# Stimulation_Testbed_Core_V1.net
KiCad netlist of a schematic drawn in EAGLE
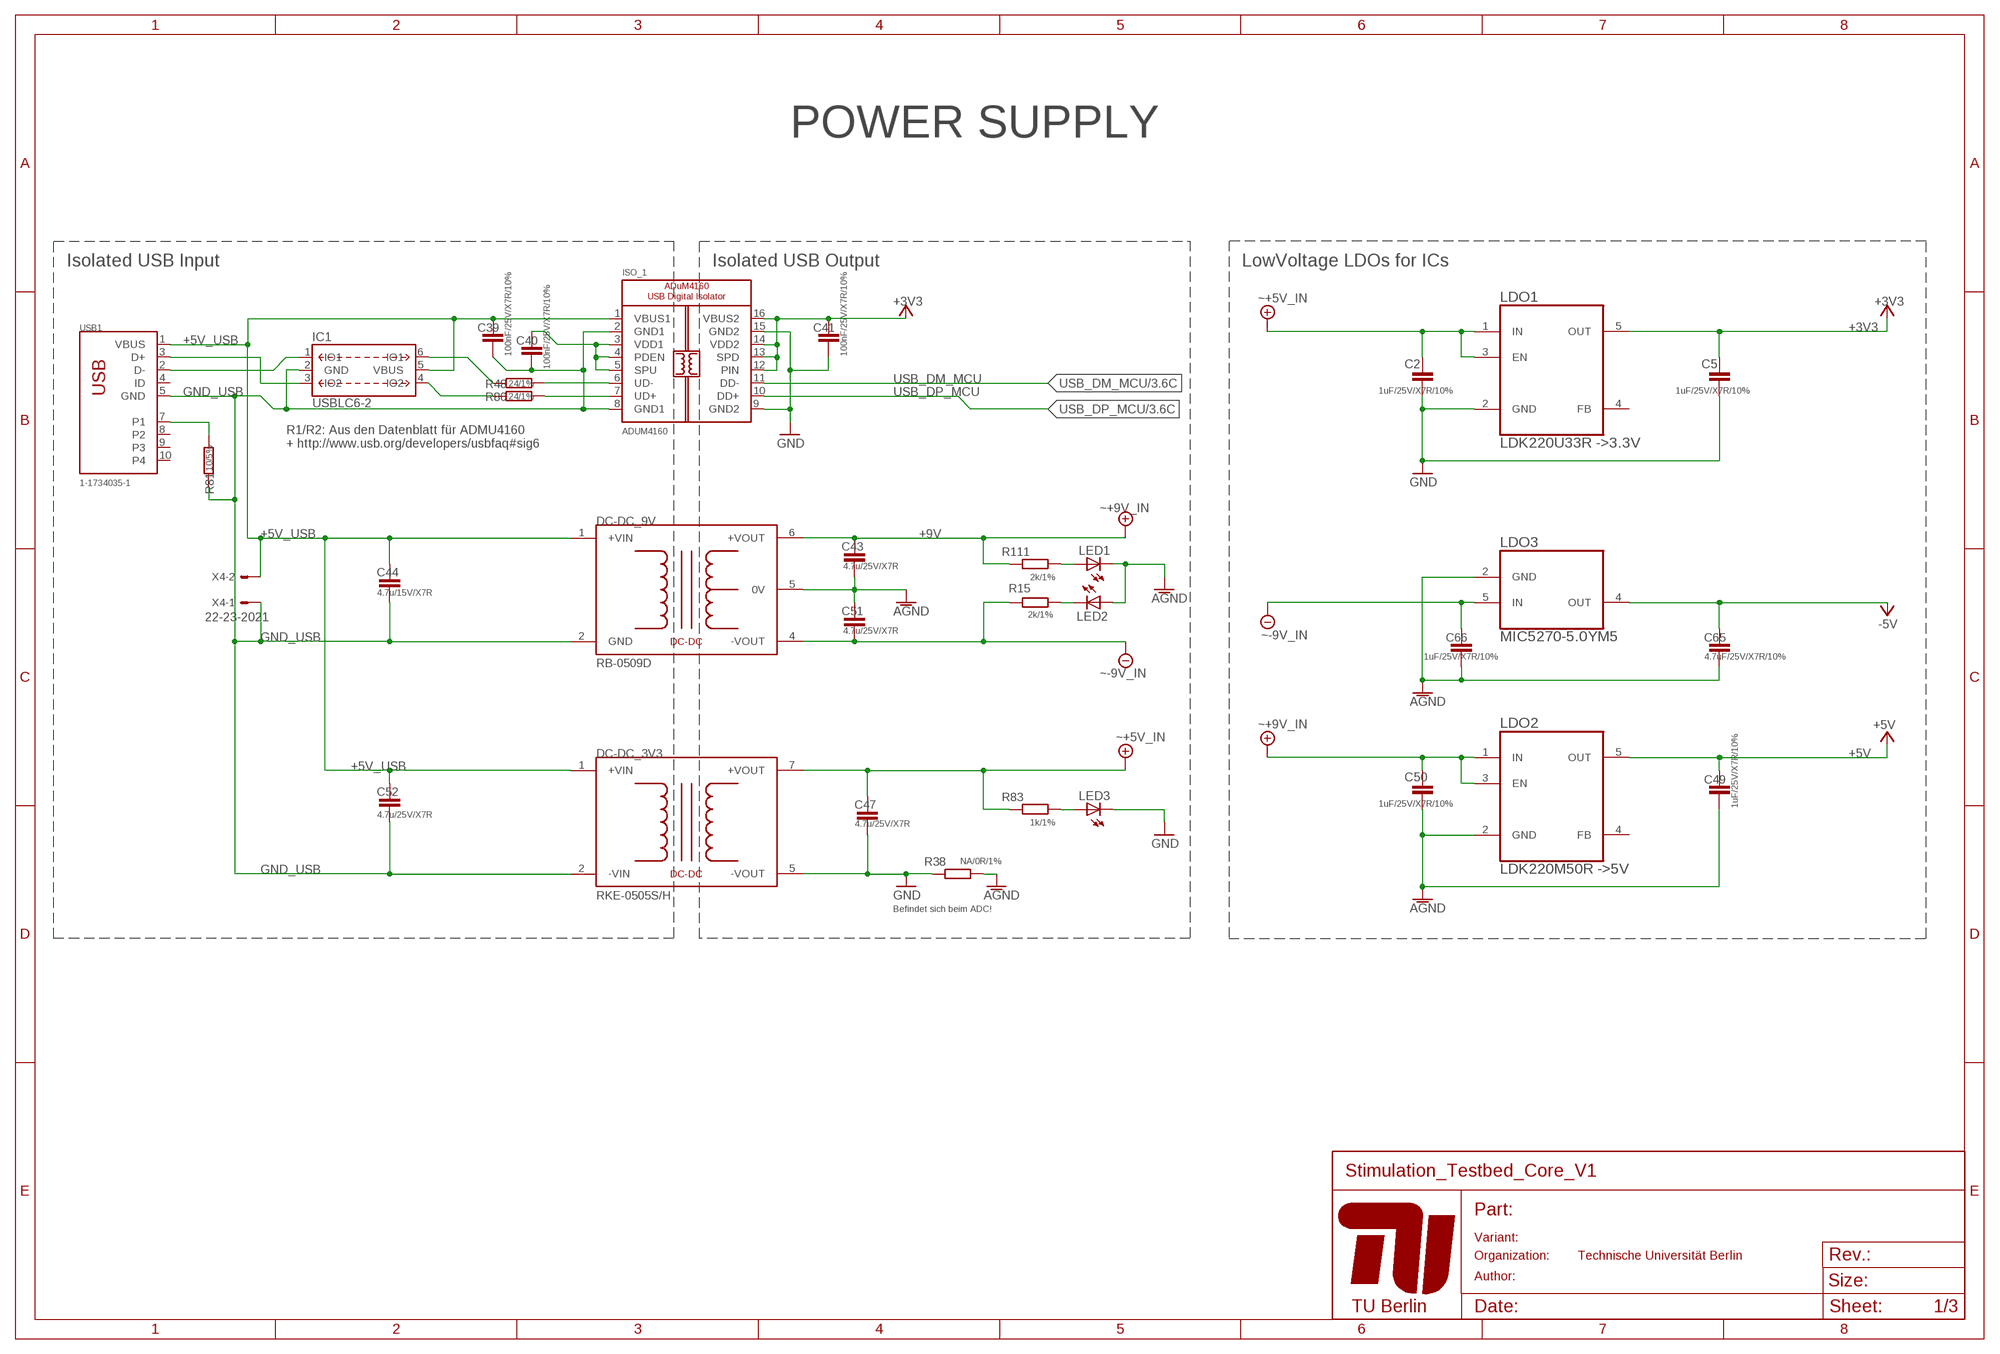
[diagram p0: schematic, sheet 1]
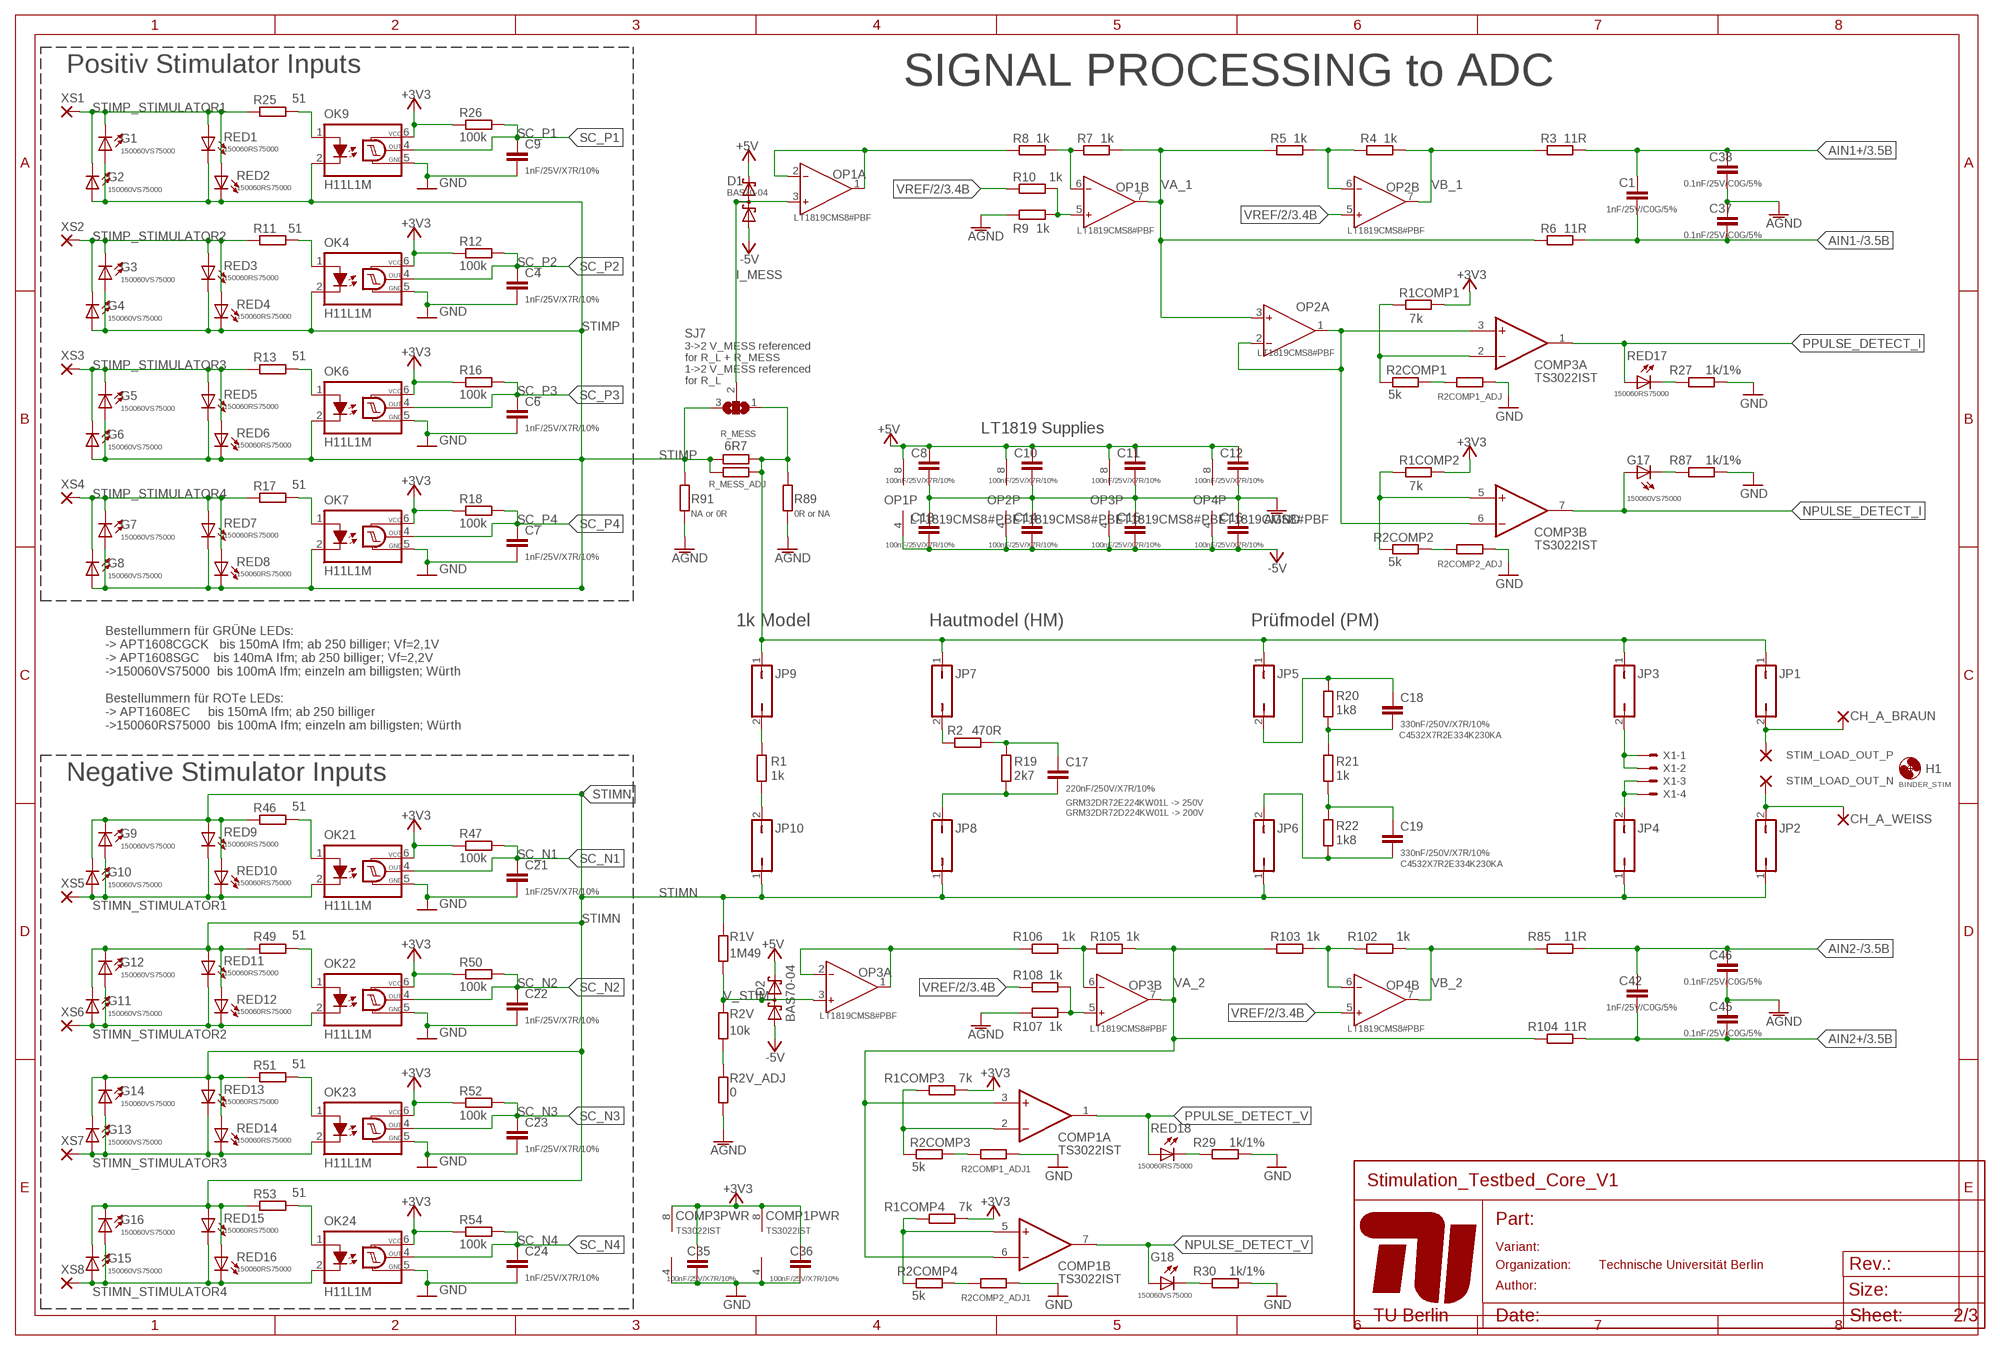
[diagram p1: schematic, sheet 2]
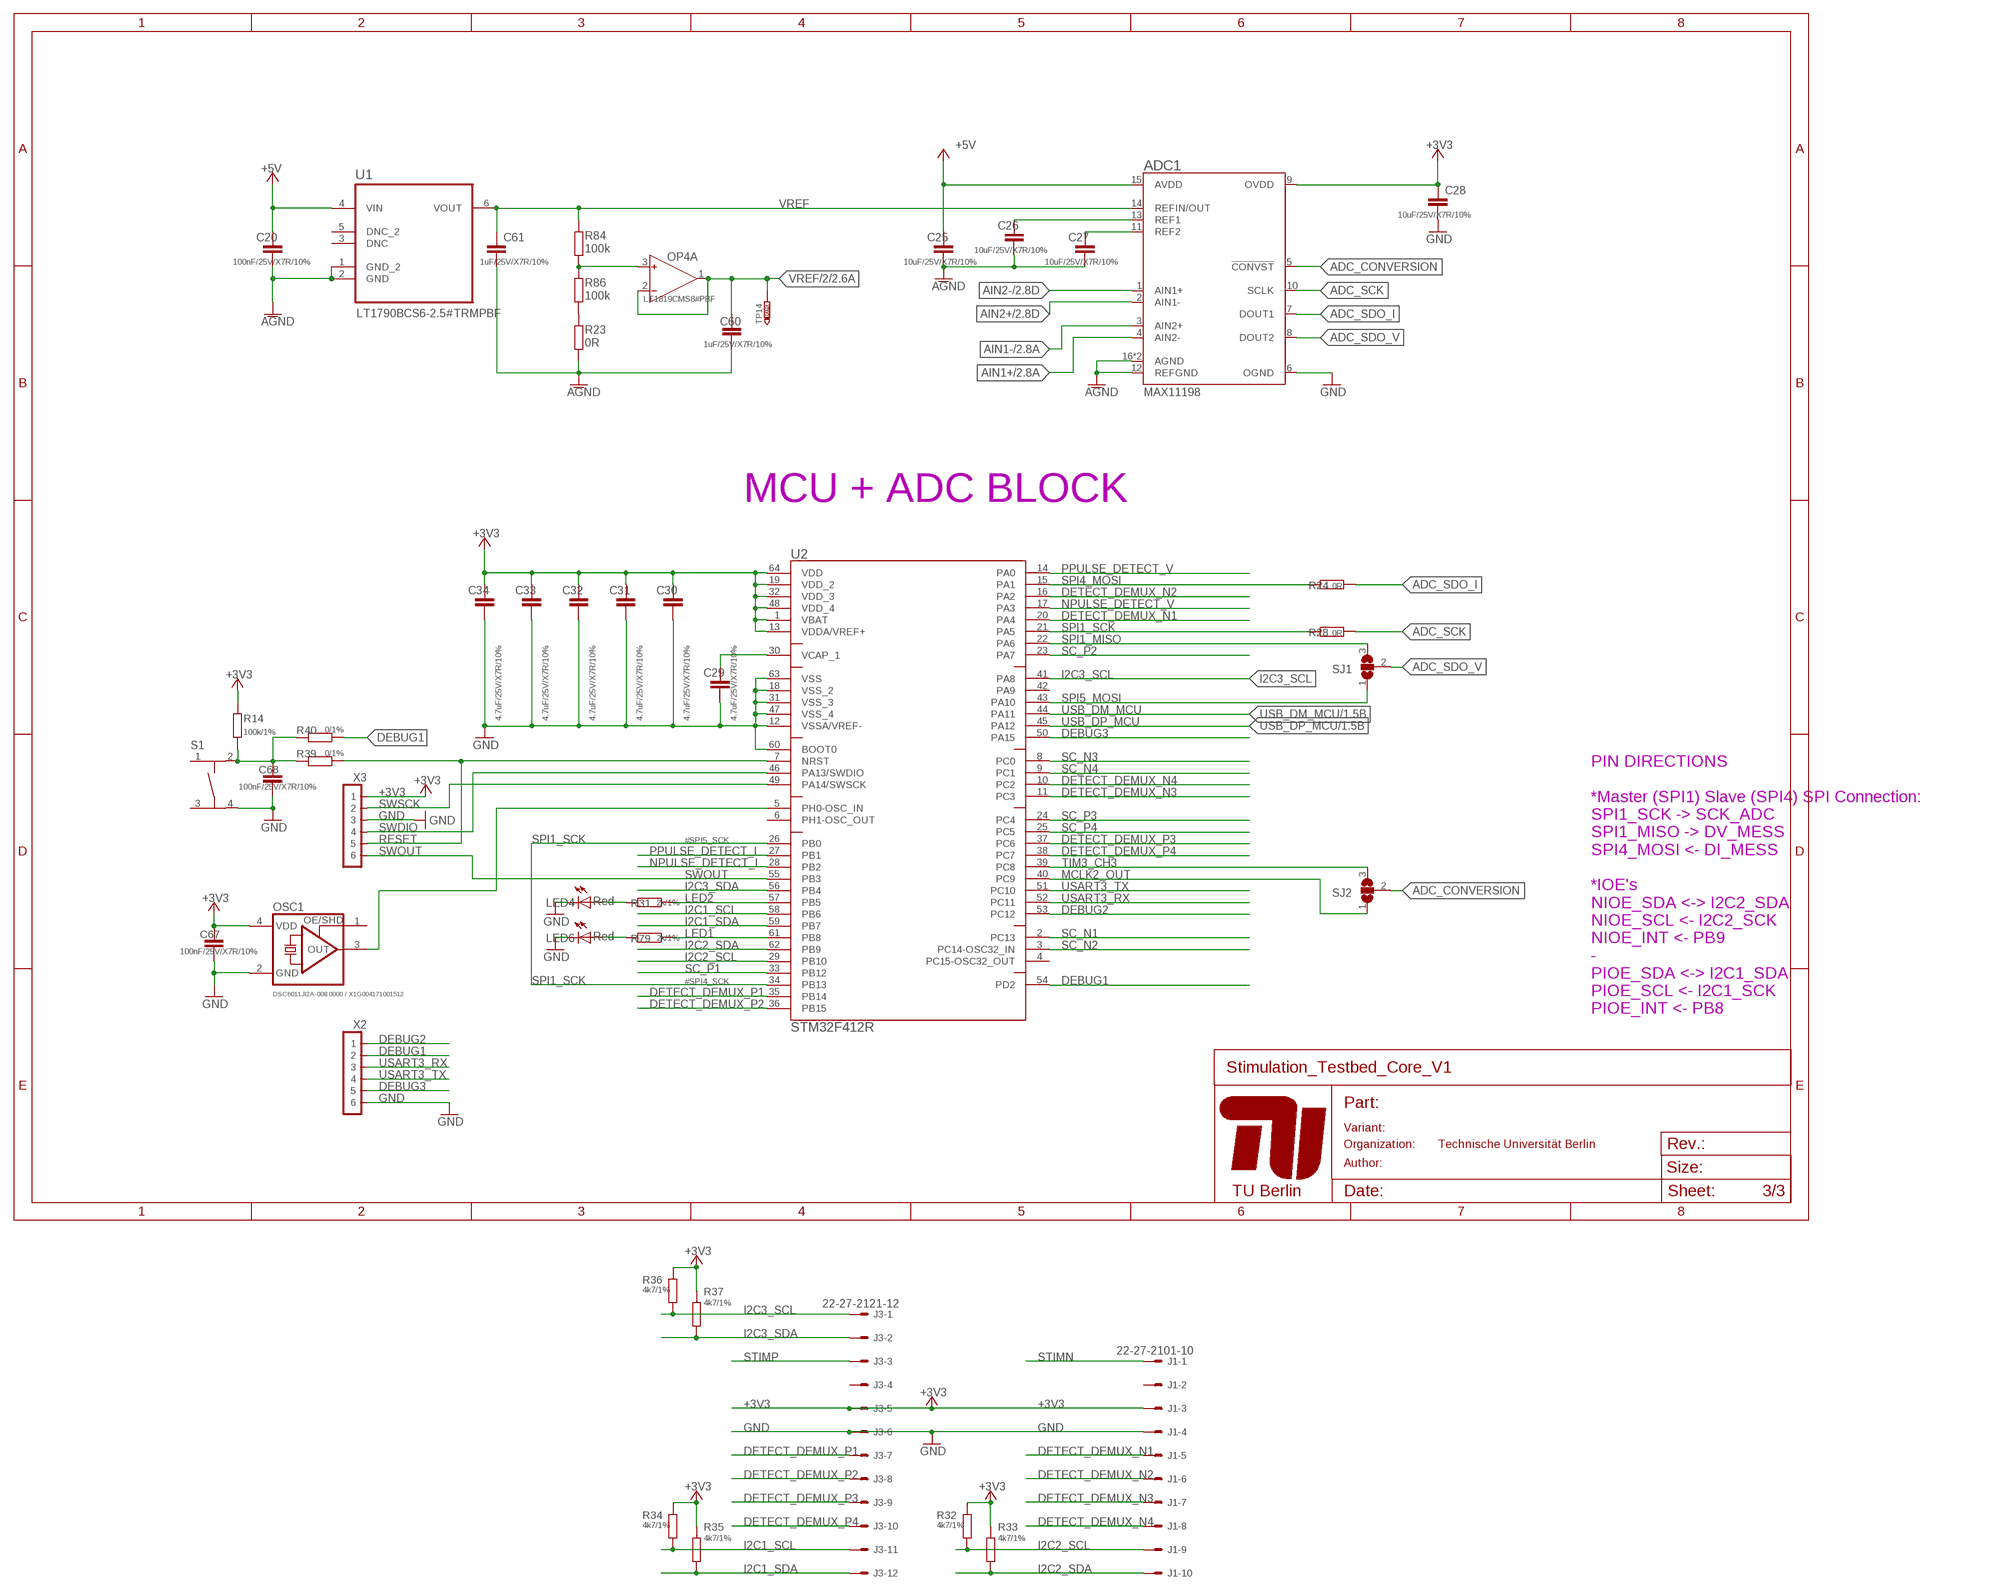
[diagram p2: schematic, sheet 3]

(export (version "E")
  (design (tool "Eeschema 10.0.6"))
  (components
    (comp (ref "ADC1")
      (value "MAX11198")
      (footprint "eagle-import:T1623CN+1")
      (libsource (lib "eagle-import") (part "MAX11198"))
    )
    (comp (ref "C20")
      (value "100nF/25V/X7R/10%")
      (footprint "eagle-import:C0603K")
      (libsource (lib "eagle-import") (part "C-EUC0603K"))
    )
    (comp (ref "C25")
      (value "10uF/25V/X7R/10%")
      (footprint "eagle-import:C0603K")
      (libsource (lib "eagle-import") (part "C-EUC0603K"))
    )
    (comp (ref "C26")
      (value "10uF/25V/X7R/10%")
      (footprint "eagle-import:C0603K")
      (libsource (lib "eagle-import") (part "C-EUC0603K"))
    )
    (comp (ref "C27")
      (value "10uF/25V/X7R/10%")
      (footprint "eagle-import:C0603K")
      (libsource (lib "eagle-import") (part "C-EUC0603K"))
    )
    (comp (ref "C28")
      (value "10uF/25V/X7R/10%")
      (footprint "eagle-import:C0603K")
      (libsource (lib "eagle-import") (part "C-EUC0603K"))
    )
    (comp (ref "C29")
      (value "4.7uF/25V/X7R/10%")
      (footprint "eagle-import:C0603K")
      (libsource (lib "eagle-import") (part "C-EUC0603K"))
    )
    (comp (ref "C30")
      (value "4.7uF/25V/X7R/10%")
      (footprint "eagle-import:C0603K")
      (libsource (lib "eagle-import") (part "C-EUC0603K"))
    )
    (comp (ref "C31")
      (value "4.7uF/25V/X7R/10%")
      (footprint "eagle-import:C0603K")
      (libsource (lib "eagle-import") (part "C-EUC0603K"))
    )
    (comp (ref "C32")
      (value "4.7uF/25V/X7R/10%")
      (footprint "eagle-import:C0603K")
      (libsource (lib "eagle-import") (part "C-EUC0603K"))
    )
    (comp (ref "C33")
      (value "4.7uF/25V/X7R/10%")
      (footprint "eagle-import:C0603K")
      (libsource (lib "eagle-import") (part "C-EUC0603K"))
    )
    (comp (ref "C34")
      (value "4.7uF/25V/X7R/10%")
      (footprint "eagle-import:C0603K")
      (libsource (lib "eagle-import") (part "C-EUC0603K"))
    )
    (comp (ref "C60")
      (value "1uF/25V/X7R/10%")
      (footprint "eagle-import:C0603K")
      (libsource (lib "eagle-import") (part "resistor_C-EUC0603K"))
    )
    (comp (ref "C61")
      (value "1uF/25V/X7R/10%")
      (footprint "eagle-import:C0603K")
      (libsource (lib "eagle-import") (part "resistor_C-EUC0603K"))
    )
    (comp (ref "C67")
      (value "100nF/25V/X7R/10%")
      (footprint "eagle-import:C0603K")
      (libsource (lib "eagle-import") (part "C-EUC0603K"))
    )
    (comp (ref "C68")
      (value "100nF/25V/X7R/10%")
      (footprint "eagle-import:C0603K")
      (libsource (lib "eagle-import") (part "C-EUC0603K"))
    )
    (comp (ref "J1")
      (value "22-27-2101-10")
      (footprint "eagle-import:6410-10")
      (libsource (lib "eagle-import") (part "22-?-1027-2101"))
    )
    (comp (ref "J3")
      (value "22-27-2121-12")
      (footprint "eagle-import:6410-12")
      (libsource (lib "eagle-import") (part "22-?-1227-2121"))
    )
    (comp (ref "LED4")
      (value "Red")
      (footprint "eagle-import:CHIPLED_0603")
      (libsource (lib "eagle-import") (part "LEDCHIPLED_0603"))
    )
    (comp (ref "LED6")
      (value "Red")
      (footprint "eagle-import:CHIPLED_0603")
      (libsource (lib "eagle-import") (part "LEDCHIPLED_0603"))
    )
    (comp (ref "OP4")
      (value "LT1819CMS8#PBF")
      (footprint "eagle-import:MSOP8")
      (libsource (lib "eagle-import") (part "LT1819"))
    )
    (comp (ref "OSC1")
      (value "DSC6011JI2A-008.0000 / X1G004171001512")
      (footprint "eagle-import:OSC_2.5X2")
      (libsource (lib "eagle-import") (part "OSC60XXX2.5X2"))
    )
    (comp (ref "R14")
      (value "100k/1%")
      (footprint "eagle-import:R0603")
      (libsource (lib "eagle-import") (part "R-EU_R0603"))
    )
    (comp (ref "R23")
      (value "0R")
      (footprint "eagle-import:R0603")
      (libsource (lib "eagle-import") (part "resistor_R-EU_R0603"))
    )
    (comp (ref "R24")
      (value "0R")
      (footprint "eagle-import:R0603")
      (libsource (lib "eagle-import") (part "R-EU_R0603"))
    )
    (comp (ref "R28")
      (value "0R")
      (footprint "eagle-import:R0603")
      (libsource (lib "eagle-import") (part "R-EU_R0603"))
    )
    (comp (ref "R31")
      (value "2k/1%")
      (footprint "eagle-import:R0603")
      (libsource (lib "eagle-import") (part "R-EU_R0603"))
    )
    (comp (ref "R32")
      (value "4k7/1%")
      (footprint "eagle-import:R0603")
      (libsource (lib "eagle-import") (part "R-EU_R0603"))
    )
    (comp (ref "R33")
      (value "4k7/1%")
      (footprint "eagle-import:R0603")
      (libsource (lib "eagle-import") (part "R-EU_R0603"))
    )
    (comp (ref "R34")
      (value "4k7/1%")
      (footprint "eagle-import:R0603")
      (libsource (lib "eagle-import") (part "R-EU_R0603"))
    )
    (comp (ref "R35")
      (value "4k7/1%")
      (footprint "eagle-import:R0603")
      (libsource (lib "eagle-import") (part "R-EU_R0603"))
    )
    (comp (ref "R36")
      (value "4k7/1%")
      (footprint "eagle-import:R0603")
      (libsource (lib "eagle-import") (part "R-EU_R0603"))
    )
    (comp (ref "R37")
      (value "4k7/1%")
      (footprint "eagle-import:R0603")
      (libsource (lib "eagle-import") (part "R-EU_R0603"))
    )
    (comp (ref "R39")
      (value "0/1%")
      (footprint "eagle-import:R0603")
      (libsource (lib "eagle-import") (part "R-EU_R0603"))
    )
    (comp (ref "R40")
      (value "0/1%")
      (footprint "eagle-import:R0603")
      (libsource (lib "eagle-import") (part "R-EU_R0603"))
    )
    (comp (ref "R79")
      (value "2k/1%")
      (footprint "eagle-import:R0603")
      (libsource (lib "eagle-import") (part "R-EU_R0603"))
    )
    (comp (ref "R84")
      (value "100k")
      (footprint "eagle-import:R0603")
      (libsource (lib "eagle-import") (part "resistor_R-EU_R0603"))
    )
    (comp (ref "R86")
      (value "100k")
      (footprint "eagle-import:R0603")
      (libsource (lib "eagle-import") (part "resistor_R-EU_R0603"))
    )
    (comp (ref "S1")
      (value "TASTERSMD")
      (footprint "eagle-import:TAST_SMD")
      (libsource (lib "eagle-import") (part "TASTERSMD"))
    )
    (comp (ref "SJ1")
      (value "SJ2W")
      (footprint "eagle-import:SJ_2")
      (libsource (lib "eagle-import") (part "SJ2W"))
    )
    (comp (ref "SJ2")
      (value "SJ2W")
      (footprint "eagle-import:SJ_2")
      (libsource (lib "eagle-import") (part "SJ2W"))
    )
    (comp (ref "TP14")
      (value "TESTPOINT_TH")
      (footprint "eagle-import:TP1-09")
      (libsource (lib "eagle-import") (part "TESTPOINT_TH"))
    )
    (comp (ref "U1")
      (value "LT1790BCS6-2.5#TRMPBF")
      (footprint "eagle-import:SOT95P280X100-6N")
      (fields (field (name "MF") "Linear Technology") (field (name "MP") "LT1790ACS6-2.5#PBF"))
      (libsource (lib "eagle-import") (part "LT1790ACS6-2.5PBF"))
    )
    (comp (ref "U2")
      (value "STM32F412R")
      (footprint "eagle-import:LQFP64-10X10MM")
      (fields (field (name "MANUFACTURER_PART_NUMBER") "stm32f4xxr2"))
      (libsource (lib "eagle-import") (part "STM32F4XXR"))
    )
    (comp (ref "X2")
      (value "PINHD-1X66X1.27")
      (footprint "eagle-import:1.27_1X06_S")
      (libsource (lib "eagle-import") (part "PINHD-1X66X1.27"))
    )
    (comp (ref "X3")
      (value "PINHD-1X66X1.27")
      (footprint "eagle-import:1.27_1X06_S")
      (libsource (lib "eagle-import") (part "PINHD-1X66X1.27"))
    )
    (comp (ref "C1")
      (value "1nF/25V/C0G/5%")
      (footprint "eagle-import:C0603K")
      (libsource (lib "eagle-import") (part "resistor_C-EUC0603K"))
    )
    (comp (ref "C4")
      (value "1nF/25V/X7R/10%")
      (footprint "eagle-import:C0603")
      (libsource (lib "eagle-import") (part "C-EUC0603"))
    )
    (comp (ref "C6")
      (value "1nF/25V/X7R/10%")
      (footprint "eagle-import:C0603")
      (libsource (lib "eagle-import") (part "C-EUC0603"))
    )
    (comp (ref "C7")
      (value "1nF/25V/X7R/10%")
      (footprint "eagle-import:C0603")
      (libsource (lib "eagle-import") (part "C-EUC0603"))
    )
    (comp (ref "C8")
      (value "100nF/25V/X7R/10%")
      (footprint "eagle-import:C0603K")
      (libsource (lib "eagle-import") (part "C-EUC0603K"))
    )
    (comp (ref "C9")
      (value "1nF/25V/X7R/10%")
      (footprint "eagle-import:C0603")
      (libsource (lib "eagle-import") (part "C-EUC0603"))
    )
    (comp (ref "C10")
      (value "100nF/25V/X7R/10%")
      (footprint "eagle-import:C0603K")
      (libsource (lib "eagle-import") (part "C-EUC0603K"))
    )
    (comp (ref "C11")
      (value "100nF/25V/X7R/10%")
      (footprint "eagle-import:C0603K")
      (libsource (lib "eagle-import") (part "C-EUC0603K"))
    )
    (comp (ref "C12")
      (value "100nF/25V/X7R/10%")
      (footprint "eagle-import:C0603K")
      (libsource (lib "eagle-import") (part "C-EUC0603K"))
    )
    (comp (ref "C13")
      (value "100nF/25V/X7R/10%")
      (footprint "eagle-import:C0603K")
      (libsource (lib "eagle-import") (part "C-EUC0603K"))
    )
    (comp (ref "C14")
      (value "100nF/25V/X7R/10%")
      (footprint "eagle-import:C0603K")
      (libsource (lib "eagle-import") (part "C-EUC0603K"))
    )
    (comp (ref "C15")
      (value "100nF/25V/X7R/10%")
      (footprint "eagle-import:C0603K")
      (libsource (lib "eagle-import") (part "C-EUC0603K"))
    )
    (comp (ref "C16")
      (value "100nF/25V/X7R/10%")
      (footprint "eagle-import:C0603K")
      (libsource (lib "eagle-import") (part "C-EUC0603K"))
    )
    (comp (ref "C17")
      (value "220nF/250V/X7R/10%")
      (footprint "eagle-import:C1210")
      (libsource (lib "eagle-import") (part "resistor_C-EUC1210"))
    )
    (comp (ref "C18")
      (value "330nF/250V/X7R/10%")
      (footprint "eagle-import:C1812")
      (libsource (lib "eagle-import") (part "resistor_C-EUC1812"))
    )
    (comp (ref "C19")
      (value "330nF/250V/X7R/10%")
      (footprint "eagle-import:C1812")
      (libsource (lib "eagle-import") (part "resistor_C-EUC1812"))
    )
    (comp (ref "C21")
      (value "1nF/25V/X7R/10%")
      (footprint "eagle-import:C0603")
      (libsource (lib "eagle-import") (part "C-EUC0603"))
    )
    (comp (ref "C22")
      (value "1nF/25V/X7R/10%")
      (footprint "eagle-import:C0603")
      (libsource (lib "eagle-import") (part "C-EUC0603"))
    )
    (comp (ref "C23")
      (value "1nF/25V/X7R/10%")
      (footprint "eagle-import:C0603")
      (libsource (lib "eagle-import") (part "C-EUC0603"))
    )
    (comp (ref "C24")
      (value "1nF/25V/X7R/10%")
      (footprint "eagle-import:C0603")
      (libsource (lib "eagle-import") (part "C-EUC0603"))
    )
    (comp (ref "C35")
      (value "100nF/25V/X7R/10%")
      (footprint "eagle-import:C0603K")
      (libsource (lib "eagle-import") (part "C-EUC0603K"))
    )
    (comp (ref "C36")
      (value "100nF/25V/X7R/10%")
      (footprint "eagle-import:C0603K")
      (libsource (lib "eagle-import") (part "C-EUC0603K"))
    )
    (comp (ref "C37")
      (value "0.1nF/25V/C0G/5%")
      (footprint "eagle-import:C0603K")
      (libsource (lib "eagle-import") (part "resistor_C-EUC0603K"))
    )
    (comp (ref "C38")
      (value "0.1nF/25V/C0G/5%")
      (footprint "eagle-import:C0603K")
      (libsource (lib "eagle-import") (part "resistor_C-EUC0603K"))
    )
    (comp (ref "C42")
      (value "1nF/25V/C0G/5%")
      (footprint "eagle-import:C0603K")
      (libsource (lib "eagle-import") (part "resistor_C-EUC0603K"))
    )
    (comp (ref "C45")
      (value "0.1nF/25V/C0G/5%")
      (footprint "eagle-import:C0603K")
      (libsource (lib "eagle-import") (part "resistor_C-EUC0603K"))
    )
    (comp (ref "C46")
      (value "0.1nF/25V/C0G/5%")
      (footprint "eagle-import:C0603K")
      (libsource (lib "eagle-import") (part "resistor_C-EUC0603K"))
    )
    (comp (ref "CH_A_BRAUN")
      (value "1,6/0,8")
      (footprint "eagle-import:1,6_0,8")
      (libsource (lib "eagle-import") (part "1,6/0,8"))
    )
    (comp (ref "CH_A_WEISS")
      (value "1,6/0,8")
      (footprint "eagle-import:1,6_0,8")
      (libsource (lib "eagle-import") (part "1,6/0,8"))
    )
    (comp (ref "COMP1")
      (value "TS3022IST")
      (footprint "eagle-import:MSOP8")
      (libsource (lib "eagle-import") (part "TS3022IST"))
    )
    (comp (ref "COMP3")
      (value "TS3022IST")
      (footprint "eagle-import:MSOP8")
      (libsource (lib "eagle-import") (part "TS3022IST"))
    )
    (comp (ref "D1")
      (value "BAS70-04")
      (footprint "eagle-import:SOT23")
      (libsource (lib "eagle-import") (part "BAS70-04"))
    )
    (comp (ref "D2")
      (value "BAS70-04")
      (footprint "eagle-import:SOT23")
      (libsource (lib "eagle-import") (part "BAS70-04"))
    )
    (comp (ref "G1")
      (value "150060VS75000")
      (footprint "eagle-import:CHIPLED_0603")
      (libsource (lib "eagle-import") (part "LEDCHIPLED_0603"))
    )
    (comp (ref "G2")
      (value "150060VS75000")
      (footprint "eagle-import:CHIPLED_0603")
      (libsource (lib "eagle-import") (part "LEDCHIPLED_0603"))
    )
    (comp (ref "G3")
      (value "150060VS75000")
      (footprint "eagle-import:CHIPLED_0603")
      (libsource (lib "eagle-import") (part "LEDCHIPLED_0603"))
    )
    (comp (ref "G4")
      (value "150060VS75000")
      (footprint "eagle-import:CHIPLED_0603")
      (libsource (lib "eagle-import") (part "LEDCHIPLED_0603"))
    )
    (comp (ref "G5")
      (value "150060VS75000")
      (footprint "eagle-import:CHIPLED_0603")
      (libsource (lib "eagle-import") (part "LEDCHIPLED_0603"))
    )
    (comp (ref "G6")
      (value "150060VS75000")
      (footprint "eagle-import:CHIPLED_0603")
      (libsource (lib "eagle-import") (part "LEDCHIPLED_0603"))
    )
    (comp (ref "G7")
      (value "150060VS75000")
      (footprint "eagle-import:CHIPLED_0603")
      (libsource (lib "eagle-import") (part "LEDCHIPLED_0603"))
    )
    (comp (ref "G8")
      (value "150060VS75000")
      (footprint "eagle-import:CHIPLED_0603")
      (libsource (lib "eagle-import") (part "LEDCHIPLED_0603"))
    )
    (comp (ref "G9")
      (value "150060VS75000")
      (footprint "eagle-import:CHIPLED_0603")
      (libsource (lib "eagle-import") (part "LEDCHIPLED_0603"))
    )
    (comp (ref "G10")
      (value "150060VS75000")
      (footprint "eagle-import:CHIPLED_0603")
      (libsource (lib "eagle-import") (part "LEDCHIPLED_0603"))
    )
    (comp (ref "G11")
      (value "150060VS75000")
      (footprint "eagle-import:CHIPLED_0603")
      (libsource (lib "eagle-import") (part "LEDCHIPLED_0603"))
    )
    (comp (ref "G12")
      (value "150060VS75000")
      (footprint "eagle-import:CHIPLED_0603")
      (libsource (lib "eagle-import") (part "LEDCHIPLED_0603"))
    )
    (comp (ref "G13")
      (value "150060VS75000")
      (footprint "eagle-import:CHIPLED_0603")
      (libsource (lib "eagle-import") (part "LEDCHIPLED_0603"))
    )
    (comp (ref "G14")
      (value "150060VS75000")
      (footprint "eagle-import:CHIPLED_0603")
      (libsource (lib "eagle-import") (part "LEDCHIPLED_0603"))
    )
    (comp (ref "G15")
      (value "150060VS75000")
      (footprint "eagle-import:CHIPLED_0603")
      (libsource (lib "eagle-import") (part "LEDCHIPLED_0603"))
    )
    (comp (ref "G16")
      (value "150060VS75000")
      (footprint "eagle-import:CHIPLED_0603")
      (libsource (lib "eagle-import") (part "LEDCHIPLED_0603"))
    )
    (comp (ref "G17")
      (value "150060VS75000")
      (footprint "eagle-import:CHIPLED_0603")
      (libsource (lib "eagle-import") (part "LEDCHIPLED_0603"))
    )
    (comp (ref "G18")
      (value "150060VS75000")
      (footprint "eagle-import:CHIPLED_0603")
      (libsource (lib "eagle-import") (part "LEDCHIPLED_0603"))
    )
    (comp (ref "H1")
      (value "BINDER_STIM")
      (footprint "eagle-import:5,5-PAD")
      (libsource (lib "eagle-import") (part "BINDER_STIM"))
    )
    (comp (ref "JP1")
      (value "JP1Q")
      (footprint "eagle-import:JP1")
      (libsource (lib "eagle-import") (part "JP1Q"))
    )
    (comp (ref "JP2")
      (value "JP1Q")
      (footprint "eagle-import:JP1")
      (libsource (lib "eagle-import") (part "JP1Q"))
    )
    (comp (ref "JP3")
      (value "JP1Q")
      (footprint "eagle-import:JP1")
      (libsource (lib "eagle-import") (part "JP1Q"))
    )
    (comp (ref "JP4")
      (value "JP1Q")
      (footprint "eagle-import:JP1")
      (libsource (lib "eagle-import") (part "JP1Q"))
    )
    (comp (ref "JP5")
      (value "JP1Q")
      (footprint "eagle-import:JP1")
      (libsource (lib "eagle-import") (part "JP1Q"))
    )
    (comp (ref "JP6")
      (value "JP1Q")
      (footprint "eagle-import:JP1")
      (libsource (lib "eagle-import") (part "JP1Q"))
    )
    (comp (ref "JP7")
      (value "JP1Q")
      (footprint "eagle-import:JP1")
      (libsource (lib "eagle-import") (part "JP1Q"))
    )
    (comp (ref "JP8")
      (value "JP1Q")
      (footprint "eagle-import:JP1")
      (libsource (lib "eagle-import") (part "JP1Q"))
    )
    (comp (ref "JP9")
      (value "JP1Q")
      (footprint "eagle-import:JP1")
      (libsource (lib "eagle-import") (part "JP1Q"))
    )
    (comp (ref "JP10")
      (value "JP1Q")
      (footprint "eagle-import:JP1")
      (libsource (lib "eagle-import") (part "JP1Q"))
    )
    (comp (ref "OK4")
      (value "H11L1M")
      (footprint "eagle-import:DIL06")
      (fields (field (name "MF") "FAIRCHILD SEMICONDUCTOR") (field (name "MPN") "H11L1-M"))
      (libsource (lib "eagle-import") (part "H11LM1"))
    )
    (comp (ref "OK6")
      (value "H11L1M")
      (footprint "eagle-import:DIL06")
      (fields (field (name "MF") "FAIRCHILD SEMICONDUCTOR") (field (name "MPN") "H11L1-M"))
      (libsource (lib "eagle-import") (part "H11LM1"))
    )
    (comp (ref "OK7")
      (value "H11L1M")
      (footprint "eagle-import:DIL06")
      (fields (field (name "MF") "FAIRCHILD SEMICONDUCTOR") (field (name "MPN") "H11L1-M"))
      (libsource (lib "eagle-import") (part "H11LM1"))
    )
    (comp (ref "OK9")
      (value "H11L1M")
      (footprint "eagle-import:DIL06")
      (fields (field (name "MF") "FAIRCHILD SEMICONDUCTOR") (field (name "MPN") "H11L1-M"))
      (libsource (lib "eagle-import") (part "H11LM1"))
    )
    (comp (ref "OK21")
      (value "H11L1M")
      (footprint "eagle-import:DIL06")
      (fields (field (name "MF") "FAIRCHILD SEMICONDUCTOR") (field (name "MPN") "H11L1-M"))
      (libsource (lib "eagle-import") (part "H11LM1"))
    )
    (comp (ref "OK22")
      (value "H11L1M")
      (footprint "eagle-import:DIL06")
      (fields (field (name "MF") "FAIRCHILD SEMICONDUCTOR") (field (name "MPN") "H11L1-M"))
      (libsource (lib "eagle-import") (part "H11LM1"))
    )
    (comp (ref "OK23")
      (value "H11L1M")
      (footprint "eagle-import:DIL06")
      (fields (field (name "MF") "FAIRCHILD SEMICONDUCTOR") (field (name "MPN") "H11L1-M"))
      (libsource (lib "eagle-import") (part "H11LM1"))
    )
    (comp (ref "OK24")
      (value "H11L1M")
      (footprint "eagle-import:DIL06")
      (fields (field (name "MF") "FAIRCHILD SEMICONDUCTOR") (field (name "MPN") "H11L1-M"))
      (libsource (lib "eagle-import") (part "H11LM1"))
    )
    (comp (ref "OP1")
      (value "LT1819CMS8#PBF")
      (footprint "eagle-import:MSOP8")
      (libsource (lib "eagle-import") (part "LT1819"))
    )
    (comp (ref "OP2")
      (value "LT1819CMS8#PBF")
      (footprint "eagle-import:MSOP8")
      (libsource (lib "eagle-import") (part "LT1819"))
    )
    (comp (ref "OP3")
      (value "LT1819CMS8#PBF")
      (footprint "eagle-import:MSOP8")
      (libsource (lib "eagle-import") (part "LT1819"))
    )
    (comp (ref "R1")
      (value "1k")
      (footprint "eagle-import:R1206")
      (libsource (lib "eagle-import") (part "resistor_R-EU_R1206"))
    )
    (comp (ref "R1COMP1")
      (value "7k")
      (footprint "eagle-import:R0603")
      (libsource (lib "eagle-import") (part "resistor_R-EU_R0603"))
    )
    (comp (ref "R1COMP2")
      (value "7k")
      (footprint "eagle-import:R0603")
      (libsource (lib "eagle-import") (part "resistor_R-EU_R0603"))
    )
    (comp (ref "R1COMP3")
      (value "7k")
      (footprint "eagle-import:R0603")
      (libsource (lib "eagle-import") (part "resistor_R-EU_R0603"))
    )
    (comp (ref "R1COMP4")
      (value "7k")
      (footprint "eagle-import:R0603")
      (libsource (lib "eagle-import") (part "resistor_R-EU_R0603"))
    )
    (comp (ref "R1V")
      (value "1M49")
      (footprint "eagle-import:R1206")
      (libsource (lib "eagle-import") (part "resistor_R-EU_R1206"))
    )
    (comp (ref "R2")
      (value "470R")
      (footprint "eagle-import:R1206")
      (libsource (lib "eagle-import") (part "resistor_R-EU_R1206"))
    )
    (comp (ref "R2COMP1")
      (value "5k")
      (footprint "eagle-import:R0603")
      (libsource (lib "eagle-import") (part "resistor_R-EU_R0603"))
    )
    (comp (ref "R2COMP1_ADJ")
      (value "R-EU_R0603")
      (footprint "eagle-import:R0603")
      (libsource (lib "eagle-import") (part "resistor_R-EU_R0603"))
    )
    (comp (ref "R2COMP1_ADJ1")
      (value "R-EU_R0603")
      (footprint "eagle-import:R0603")
      (libsource (lib "eagle-import") (part "resistor_R-EU_R0603"))
    )
    (comp (ref "R2COMP2")
      (value "5k")
      (footprint "eagle-import:R0603")
      (libsource (lib "eagle-import") (part "resistor_R-EU_R0603"))
    )
    (comp (ref "R2COMP2_ADJ")
      (value "1k")
      (footprint "eagle-import:R0603")
      (libsource (lib "eagle-import") (part "resistor_R-EU_R0603"))
    )
    (comp (ref "R2COMP2_ADJ1")
      (value "1k")
      (footprint "eagle-import:R0603")
      (libsource (lib "eagle-import") (part "resistor_R-EU_R0603"))
    )
    (comp (ref "R2COMP3")
      (value "5k")
      (footprint "eagle-import:R0603")
      (libsource (lib "eagle-import") (part "resistor_R-EU_R0603"))
    )
    (comp (ref "R2COMP4")
      (value "5k")
      (footprint "eagle-import:R0603")
      (libsource (lib "eagle-import") (part "resistor_R-EU_R0603"))
    )
    (comp (ref "R2V")
      (value "10k")
      (footprint "eagle-import:R1206")
      (libsource (lib "eagle-import") (part "resistor_R-EU_R1206"))
    )
    (comp (ref "R2V_ADJ")
      (value "0")
      (footprint "eagle-import:R1206")
      (libsource (lib "eagle-import") (part "resistor_R-EU_R1206"))
    )
    (comp (ref "R3")
      (value "11R")
      (footprint "eagle-import:R0603")
      (libsource (lib "eagle-import") (part "resistor_R-EU_R0603"))
    )
    (comp (ref "R4")
      (value "1k")
      (footprint "eagle-import:R0603")
      (libsource (lib "eagle-import") (part "resistor_R-EU_R0603"))
    )
    (comp (ref "R5")
      (value "1k")
      (footprint "eagle-import:R0603")
      (libsource (lib "eagle-import") (part "resistor_R-EU_R0603"))
    )
    (comp (ref "R6")
      (value "11R")
      (footprint "eagle-import:R0603")
      (libsource (lib "eagle-import") (part "resistor_R-EU_R0603"))
    )
    (comp (ref "R7")
      (value "1k")
      (footprint "eagle-import:R0603")
      (libsource (lib "eagle-import") (part "resistor_R-EU_R0603"))
    )
    (comp (ref "R8")
      (value "1k")
      (footprint "eagle-import:R0603")
      (libsource (lib "eagle-import") (part "resistor_R-EU_R0603"))
    )
    (comp (ref "R9")
      (value "1k")
      (footprint "eagle-import:R0603")
      (libsource (lib "eagle-import") (part "resistor_R-EU_R0603"))
    )
    (comp (ref "R10")
      (value "1k")
      (footprint "eagle-import:R0603")
      (libsource (lib "eagle-import") (part "resistor_R-EU_R0603"))
    )
    (comp (ref "R11")
      (value "51")
      (footprint "eagle-import:R0603")
      (libsource (lib "eagle-import") (part "resistor_R-EU_R0603"))
    )
    (comp (ref "R12")
      (value "100k")
      (footprint "eagle-import:R0603")
      (libsource (lib "eagle-import") (part "resistor_R-EU_R0603"))
    )
    (comp (ref "R13")
      (value "51")
      (footprint "eagle-import:R0603")
      (libsource (lib "eagle-import") (part "resistor_R-EU_R0603"))
    )
    (comp (ref "R16")
      (value "100k")
      (footprint "eagle-import:R0603")
      (libsource (lib "eagle-import") (part "resistor_R-EU_R0603"))
    )
    (comp (ref "R17")
      (value "51")
      (footprint "eagle-import:R0603")
      (libsource (lib "eagle-import") (part "resistor_R-EU_R0603"))
    )
    (comp (ref "R18")
      (value "100k")
      (footprint "eagle-import:R0603")
      (libsource (lib "eagle-import") (part "resistor_R-EU_R0603"))
    )
    (comp (ref "R19")
      (value "2k7")
      (footprint "eagle-import:R1206")
      (libsource (lib "eagle-import") (part "resistor_R-EU_R1206"))
    )
    (comp (ref "R20")
      (value "1k8")
      (footprint "eagle-import:R1206")
      (libsource (lib "eagle-import") (part "resistor_R-EU_R1206"))
    )
    (comp (ref "R21")
      (value "1k")
      (footprint "eagle-import:R1206")
      (libsource (lib "eagle-import") (part "resistor_R-EU_R1206"))
    )
    (comp (ref "R22")
      (value "1k8")
      (footprint "eagle-import:R1206")
      (libsource (lib "eagle-import") (part "resistor_R-EU_R1206"))
    )
    (comp (ref "R25")
      (value "51")
      (footprint "eagle-import:R0603")
      (libsource (lib "eagle-import") (part "resistor_R-EU_R0603"))
    )
    (comp (ref "R26")
      (value "100k")
      (footprint "eagle-import:R0603")
      (libsource (lib "eagle-import") (part "resistor_R-EU_R0603"))
    )
    (comp (ref "R27")
      (value "1k/1%")
      (footprint "eagle-import:R0603")
      (libsource (lib "eagle-import") (part "resistor_R-EU_R0603"))
    )
    (comp (ref "R29")
      (value "1k/1%")
      (footprint "eagle-import:R0603")
      (libsource (lib "eagle-import") (part "resistor_R-EU_R0603"))
    )
    (comp (ref "R30")
      (value "1k/1%")
      (footprint "eagle-import:R0603")
      (libsource (lib "eagle-import") (part "resistor_R-EU_R0603"))
    )
    (comp (ref "R46")
      (value "51")
      (footprint "eagle-import:R0603")
      (libsource (lib "eagle-import") (part "resistor_R-EU_R0603"))
    )
    (comp (ref "R47")
      (value "100k")
      (footprint "eagle-import:R0603")
      (libsource (lib "eagle-import") (part "resistor_R-EU_R0603"))
    )
    (comp (ref "R49")
      (value "51")
      (footprint "eagle-import:R0603")
      (libsource (lib "eagle-import") (part "resistor_R-EU_R0603"))
    )
    (comp (ref "R50")
      (value "100k")
      (footprint "eagle-import:R0603")
      (libsource (lib "eagle-import") (part "resistor_R-EU_R0603"))
    )
    (comp (ref "R51")
      (value "51")
      (footprint "eagle-import:R0603")
      (libsource (lib "eagle-import") (part "resistor_R-EU_R0603"))
    )
    (comp (ref "R52")
      (value "100k")
      (footprint "eagle-import:R0603")
      (libsource (lib "eagle-import") (part "resistor_R-EU_R0603"))
    )
    (comp (ref "R53")
      (value "51")
      (footprint "eagle-import:R0603")
      (libsource (lib "eagle-import") (part "resistor_R-EU_R0603"))
    )
    (comp (ref "R54")
      (value "100k")
      (footprint "eagle-import:R0603")
      (libsource (lib "eagle-import") (part "resistor_R-EU_R0603"))
    )
    (comp (ref "R85")
      (value "11R")
      (footprint "eagle-import:R0603")
      (libsource (lib "eagle-import") (part "resistor_R-EU_R0603"))
    )
    (comp (ref "R87")
      (value "1k/1%")
      (footprint "eagle-import:R0603")
      (libsource (lib "eagle-import") (part "resistor_R-EU_R0603"))
    )
    (comp (ref "R89")
      (value "0R or NA")
      (footprint "eagle-import:R0603")
      (libsource (lib "eagle-import") (part "resistor_R-EU_R0603"))
    )
    (comp (ref "R91")
      (value "NA or 0R")
      (footprint "eagle-import:R0603")
      (libsource (lib "eagle-import") (part "resistor_R-EU_R0603"))
    )
    (comp (ref "R102")
      (value "1k")
      (footprint "eagle-import:R0603")
      (libsource (lib "eagle-import") (part "resistor_R-EU_R0603"))
    )
    (comp (ref "R103")
      (value "1k")
      (footprint "eagle-import:R0603")
      (libsource (lib "eagle-import") (part "resistor_R-EU_R0603"))
    )
    (comp (ref "R104")
      (value "11R")
      (footprint "eagle-import:R0603")
      (libsource (lib "eagle-import") (part "resistor_R-EU_R0603"))
    )
    (comp (ref "R105")
      (value "1k")
      (footprint "eagle-import:R0603")
      (libsource (lib "eagle-import") (part "resistor_R-EU_R0603"))
    )
    (comp (ref "R106")
      (value "1k")
      (footprint "eagle-import:R0603")
      (libsource (lib "eagle-import") (part "resistor_R-EU_R0603"))
    )
    (comp (ref "R107")
      (value "1k")
      (footprint "eagle-import:R0603")
      (libsource (lib "eagle-import") (part "resistor_R-EU_R0603"))
    )
    (comp (ref "R108")
      (value "1k")
      (footprint "eagle-import:R0603")
      (libsource (lib "eagle-import") (part "resistor_R-EU_R0603"))
    )
    (comp (ref "RED1")
      (value "150060RS75000")
      (footprint "eagle-import:CHIP-LED0603")
      (libsource (lib "eagle-import") (part "LEDCHIP-LED0603"))
    )
    (comp (ref "RED2")
      (value "150060RS75000")
      (footprint "eagle-import:CHIP-LED0603")
      (libsource (lib "eagle-import") (part "LEDCHIP-LED0603"))
    )
    (comp (ref "RED3")
      (value "150060RS75000")
      (footprint "eagle-import:CHIP-LED0603")
      (libsource (lib "eagle-import") (part "LEDCHIP-LED0603"))
    )
    (comp (ref "RED4")
      (value "150060RS75000")
      (footprint "eagle-import:CHIP-LED0603")
      (libsource (lib "eagle-import") (part "LEDCHIP-LED0603"))
    )
    (comp (ref "RED5")
      (value "150060RS75000")
      (footprint "eagle-import:CHIP-LED0603")
      (libsource (lib "eagle-import") (part "LEDCHIP-LED0603"))
    )
    (comp (ref "RED6")
      (value "150060RS75000")
      (footprint "eagle-import:CHIP-LED0603")
      (libsource (lib "eagle-import") (part "LEDCHIP-LED0603"))
    )
    (comp (ref "RED7")
      (value "150060RS75000")
      (footprint "eagle-import:CHIP-LED0603")
      (libsource (lib "eagle-import") (part "LEDCHIP-LED0603"))
    )
    (comp (ref "RED8")
      (value "150060RS75000")
      (footprint "eagle-import:CHIP-LED0603")
      (libsource (lib "eagle-import") (part "LEDCHIP-LED0603"))
    )
    (comp (ref "RED9")
      (value "150060RS75000")
      (footprint "eagle-import:CHIP-LED0603")
      (libsource (lib "eagle-import") (part "LEDCHIP-LED0603"))
    )
    (comp (ref "RED10")
      (value "150060RS75000")
      (footprint "eagle-import:CHIP-LED0603")
      (libsource (lib "eagle-import") (part "LEDCHIP-LED0603"))
    )
    (comp (ref "RED11")
      (value "150060RS75000")
      (footprint "eagle-import:CHIP-LED0603")
      (libsource (lib "eagle-import") (part "LEDCHIP-LED0603"))
    )
    (comp (ref "RED12")
      (value "150060RS75000")
      (footprint "eagle-import:CHIP-LED0603")
      (libsource (lib "eagle-import") (part "LEDCHIP-LED0603"))
    )
    (comp (ref "RED13")
      (value "150060RS75000")
      (footprint "eagle-import:CHIP-LED0603")
      (libsource (lib "eagle-import") (part "LEDCHIP-LED0603"))
    )
    (comp (ref "RED14")
      (value "150060RS75000")
      (footprint "eagle-import:CHIP-LED0603")
      (libsource (lib "eagle-import") (part "LEDCHIP-LED0603"))
    )
    (comp (ref "RED15")
      (value "150060RS75000")
      (footprint "eagle-import:CHIP-LED0603")
      (libsource (lib "eagle-import") (part "LEDCHIP-LED0603"))
    )
    (comp (ref "RED16")
      (value "150060RS75000")
      (footprint "eagle-import:CHIP-LED0603")
      (libsource (lib "eagle-import") (part "LEDCHIP-LED0603"))
    )
    (comp (ref "RED17")
      (value "150060RS75000")
      (footprint "eagle-import:CHIP-LED0603")
      (libsource (lib "eagle-import") (part "LEDCHIP-LED0603"))
    )
    (comp (ref "RED18")
      (value "150060RS75000")
      (footprint "eagle-import:CHIP-LED0603")
      (libsource (lib "eagle-import") (part "LEDCHIP-LED0603"))
    )
    (comp (ref "R_MESS")
      (value "6R7")
      (footprint "eagle-import:R1206")
      (libsource (lib "eagle-import") (part "resistor_R-EU_R1206"))
    )
    (comp (ref "R_MESS_ADJ")
      (value "R-EU_R1206")
      (footprint "eagle-import:R1206")
      (libsource (lib "eagle-import") (part "resistor_R-EU_R1206"))
    )
    (comp (ref "SJ7")
      (value "SJ2W")
      (footprint "eagle-import:SJ_2")
      (libsource (lib "eagle-import") (part "SJ2W"))
    )
    (comp (ref "STIM_LOAD_OUT_N")
      (value "3,81/1,4")
      (footprint "eagle-import:3,81_1,4")
      (libsource (lib "eagle-import") (part "3,81/1,4"))
    )
    (comp (ref "STIM_LOAD_OUT_P")
      (value "3,81/1,4")
      (footprint "eagle-import:3,81_1,4")
      (libsource (lib "eagle-import") (part "3,81/1,4"))
    )
    (comp (ref "X1")
      (value "22-23-2041")
      (footprint "eagle-import:22-23-2041")
      (fields (field (name "MF") "MOLEX"))
      (libsource (lib "eagle-import") (part "22-23-2041"))
    )
    (comp (ref "XS1")
      (value "WIREPAD3,81/1,4")
      (footprint "eagle-import:3,81_1,4")
      (libsource (lib "eagle-import") (part "WIREPAD3,81/1,4"))
    )
    (comp (ref "XS2")
      (value "WIREPAD3,81/1,4")
      (footprint "eagle-import:3,81_1,4")
      (libsource (lib "eagle-import") (part "WIREPAD3,81/1,4"))
    )
    (comp (ref "XS3")
      (value "WIREPAD3,81/1,4")
      (footprint "eagle-import:3,81_1,4")
      (libsource (lib "eagle-import") (part "WIREPAD3,81/1,4"))
    )
    (comp (ref "XS4")
      (value "WIREPAD3,81/1,4")
      (footprint "eagle-import:3,81_1,4")
      (libsource (lib "eagle-import") (part "WIREPAD3,81/1,4"))
    )
    (comp (ref "XS5")
      (value "WIREPAD3,81/1,4")
      (footprint "eagle-import:3,81_1,4")
      (libsource (lib "eagle-import") (part "WIREPAD3,81/1,4"))
    )
    (comp (ref "XS6")
      (value "WIREPAD3,81/1,4")
      (footprint "eagle-import:3,81_1,4")
      (libsource (lib "eagle-import") (part "WIREPAD3,81/1,4"))
    )
    (comp (ref "XS7")
      (value "WIREPAD3,81/1,4")
      (footprint "eagle-import:3,81_1,4")
      (libsource (lib "eagle-import") (part "WIREPAD3,81/1,4"))
    )
    (comp (ref "XS8")
      (value "WIREPAD3,81/1,4")
      (footprint "eagle-import:3,81_1,4")
      (libsource (lib "eagle-import") (part "WIREPAD3,81/1,4"))
    )
    (comp (ref "C2")
      (value "1uF/25V/X7R/10%")
      (footprint "eagle-import:C0603K")
      (libsource (lib "eagle-import") (part "C-EUC0603K"))
    )
    (comp (ref "C5")
      (value "1uF/25V/X7R/10%")
      (footprint "eagle-import:C0603K")
      (libsource (lib "eagle-import") (part "C-EUC0603K"))
    )
    (comp (ref "C39")
      (value "100nF/25V/X7R/10%")
      (footprint "eagle-import:C0603K")
      (libsource (lib "eagle-import") (part "C-EUC0603K"))
    )
    (comp (ref "C40")
      (value "100nF/25V/X7R/10%")
      (footprint "eagle-import:C0603K")
      (libsource (lib "eagle-import") (part "C-EUC0603K"))
    )
    (comp (ref "C41")
      (value "100nF/25V/X7R/10%")
      (footprint "eagle-import:C0603K")
      (libsource (lib "eagle-import") (part "C-EUC0603K"))
    )
    (comp (ref "C43")
      (value "4.7u/25V/X7R")
      (footprint "eagle-import:C0603")
      (libsource (lib "eagle-import") (part "C-EUC0603"))
    )
    (comp (ref "C44")
      (value "4.7u/15V/X7R")
      (footprint "eagle-import:C0603")
      (libsource (lib "eagle-import") (part "C-EUC0603"))
    )
    (comp (ref "C47")
      (value "4.7u/25V/X7R")
      (footprint "eagle-import:C0603")
      (libsource (lib "eagle-import") (part "C-EUC0603"))
    )
    (comp (ref "C49")
      (value "1uF/25V/X7R/10%")
      (footprint "eagle-import:C0603K")
      (libsource (lib "eagle-import") (part "C-EUC0603K"))
    )
    (comp (ref "C50")
      (value "1uF/25V/X7R/10%")
      (footprint "eagle-import:C0603K")
      (libsource (lib "eagle-import") (part "C-EUC0603K"))
    )
    (comp (ref "C51")
      (value "4.7u/25V/X7R")
      (footprint "eagle-import:C0603")
      (libsource (lib "eagle-import") (part "C-EUC0603"))
    )
    (comp (ref "C52")
      (value "4.7u/25V/X7R")
      (footprint "eagle-import:C0603")
      (libsource (lib "eagle-import") (part "C-EUC0603"))
    )
    (comp (ref "C65")
      (value "4.7uF/25V/X7R/10%")
      (footprint "eagle-import:C0603K")
      (libsource (lib "eagle-import") (part "C-EUC0603K"))
    )
    (comp (ref "C66")
      (value "1uF/25V/X7R/10%")
      (footprint "eagle-import:C0603K")
      (libsource (lib "eagle-import") (part "C-EUC0603K"))
    )
    (comp (ref "DC-DC_3V3")
      (value "RKE-0505S/H")
      (footprint "eagle-import:MEJ2")
      (libsource (lib "eagle-import") (part "MEJ2S0503SC"))
    )
    (comp (ref "DC-DC_9V")
      (value "RB-0509D")
      (footprint "eagle-import:NMH")
      (libsource (lib "eagle-import") (part "NMH0509SC"))
    )
    (comp (ref "IC1")
      (value "USBLC6-2")
      (footprint "eagle-import:SOT-23-6")
      (libsource (lib "eagle-import") (part "USBLC6-2"))
    )
    (comp (ref "ISO_1")
      (value "ADUM4160")
      (footprint "eagle-import:SOIC16WIDE")
      (libsource (lib "eagle-import") (part "ADMU4160"))
    )
    (comp (ref "LDO1")
      (value "LDK220U33R ->3.3V")
      (footprint "eagle-import:SOT-23-5")
      (libsource (lib "eagle-import") (part "LDK220"))
    )
    (comp (ref "LDO2")
      (value "LDK220M50R ->5V")
      (footprint "eagle-import:SOT-23-5")
      (libsource (lib "eagle-import") (part "LDK220"))
    )
    (comp (ref "LDO3")
      (value "MIC5270-5.0YM5")
      (footprint "eagle-import:SOT-23-5")
      (libsource (lib "eagle-import") (part "MIC5270-X.X"))
    )
    (comp (ref "LED1")
      (value "LEDCHIPLED_0603")
      (footprint "eagle-import:CHIPLED_0603")
      (libsource (lib "eagle-import") (part "LEDCHIPLED_0603"))
    )
    (comp (ref "LED2")
      (value "LEDCHIPLED_0603")
      (footprint "eagle-import:CHIPLED_0603")
      (libsource (lib "eagle-import") (part "LEDCHIPLED_0603"))
    )
    (comp (ref "LED3")
      (value "LEDCHIPLED_0603")
      (footprint "eagle-import:CHIPLED_0603")
      (libsource (lib "eagle-import") (part "LEDCHIPLED_0603"))
    )
    (comp (ref "R15")
      (value "2k/1%")
      (footprint "eagle-import:R0603")
      (libsource (lib "eagle-import") (part "R-EU_R0603"))
    )
    (comp (ref "R38")
      (value "NA/0R/1%")
      (footprint "eagle-import:R0603")
      (libsource (lib "eagle-import") (part "R-EU_R0603"))
    )
    (comp (ref "R48")
      (value "24/1%")
      (footprint "eagle-import:R0603")
      (libsource (lib "eagle-import") (part "R-EU_R0603"))
    )
    (comp (ref "R80")
      (value "24/1%")
      (footprint "eagle-import:R0603")
      (libsource (lib "eagle-import") (part "R-EU_R0603"))
    )
    (comp (ref "R81")
      (value "10/5%")
      (footprint "eagle-import:R0603")
      (libsource (lib "eagle-import") (part "R-EU_R0603"))
    )
    (comp (ref "R83")
      (value "1k/1%")
      (footprint "eagle-import:R0603")
      (libsource (lib "eagle-import") (part "R-EU_R0603"))
    )
    (comp (ref "R111")
      (value "2k/1%")
      (footprint "eagle-import:R0603")
      (libsource (lib "eagle-import") (part "R-EU_R0603"))
    )
    (comp (ref "USB1")
      (value "1-1734035-1")
      (footprint "eagle-import:TE_1-1734035-1")
      (fields (field (name "DIGI-KEY_PART_NUMBER") "A123089-ND") (field (name "MF") "TE Connectivity"))
      (libsource (lib "eagle-import") (part "1-1734035-1"))
    )
    (comp (ref "X4")
      (value "22-23-2021")
      (footprint "eagle-import:22-23-2021")
      (fields (field (name "MF") "MOLEX"))
      (libsource (lib "eagle-import") (part "22-23-2021"))
    )
  )
  (nets
    (net (code "1") (name "+3V3") (class "Default")
      (node (ref "ADC1") (pin "9") (pinfunction "OVDD_9") (pintype "power_in"))
      (node (ref "C28") (pin "1") (pinfunction "1_1") (pintype "passive"))
      (node (ref "C30") (pin "1") (pinfunction "1_1") (pintype "passive"))
      (node (ref "C31") (pin "1") (pinfunction "1_1") (pintype "passive"))
      (node (ref "C32") (pin "1") (pinfunction "1_1") (pintype "passive"))
      (node (ref "C33") (pin "1") (pinfunction "1_1") (pintype "passive"))
      (node (ref "C34") (pin "1") (pinfunction "1_1") (pintype "passive"))
      (node (ref "C35") (pin "1") (pinfunction "1_1") (pintype "passive"))
      (node (ref "C36") (pin "1") (pinfunction "1_1") (pintype "passive"))
      (node (ref "C41") (pin "1") (pinfunction "1_1") (pintype "passive"))
      (node (ref "C5") (pin "1") (pinfunction "1_1") (pintype "passive"))
      (node (ref "C67") (pin "1") (pinfunction "1_1") (pintype "passive"))
      (node (ref "COMP1") (pin "8") (pinfunction "V+_8") (pintype "power_in"))
      (node (ref "COMP3") (pin "8") (pinfunction "V+_8") (pintype "power_in"))
      (node (ref "ISO_1") (pin "12") (pinfunction "PIN_12") (pintype "input"))
      (node (ref "ISO_1") (pin "13") (pinfunction "SPD_13") (pintype "input"))
      (node (ref "ISO_1") (pin "14") (pinfunction "VDD2_14") (pintype "power_in"))
      (node (ref "ISO_1") (pin "16") (pinfunction "VBUS2_16") (pintype "power_in"))
      (node (ref "J1") (pin "3") (pinfunction "S_3") (pintype "passive"))
      (node (ref "J3") (pin "5") (pinfunction "S_5") (pintype "passive"))
      (node (ref "LDO1") (pin "5") (pinfunction "OUT_5") (pintype "power_in"))
      (node (ref "OK21") (pin "6") (pinfunction "VCC_6") (pintype "power_in"))
      (node (ref "OK22") (pin "6") (pinfunction "VCC_6") (pintype "power_in"))
      (node (ref "OK23") (pin "6") (pinfunction "VCC_6") (pintype "power_in"))
      (node (ref "OK24") (pin "6") (pinfunction "VCC_6") (pintype "power_in"))
      (node (ref "OK4") (pin "6") (pinfunction "VCC_6") (pintype "power_in"))
      (node (ref "OK6") (pin "6") (pinfunction "VCC_6") (pintype "power_in"))
      (node (ref "OK7") (pin "6") (pinfunction "VCC_6") (pintype "power_in"))
      (node (ref "OK9") (pin "6") (pinfunction "VCC_6") (pintype "power_in"))
      (node (ref "OSC1") (pin "4") (pinfunction "VDD_4") (pintype "power_in"))
      (node (ref "R12") (pin "1") (pinfunction "1_1") (pintype "passive"))
      (node (ref "R14") (pin "2") (pinfunction "2_2") (pintype "passive"))
      (node (ref "R16") (pin "1") (pinfunction "1_1") (pintype "passive"))
      (node (ref "R18") (pin "1") (pinfunction "1_1") (pintype "passive"))
      (node (ref "R1COMP1") (pin "1") (pinfunction "1_1") (pintype "passive"))
      (node (ref "R1COMP2") (pin "1") (pinfunction "1_1") (pintype "passive"))
      (node (ref "R1COMP3") (pin "1") (pinfunction "1_1") (pintype "passive"))
      (node (ref "R1COMP4") (pin "1") (pinfunction "1_1") (pintype "passive"))
      (node (ref "R26") (pin "1") (pinfunction "1_1") (pintype "passive"))
      (node (ref "R32") (pin "1") (pinfunction "1_1") (pintype "passive"))
      (node (ref "R33") (pin "1") (pinfunction "1_1") (pintype "passive"))
      (node (ref "R34") (pin "1") (pinfunction "1_1") (pintype "passive"))
      (node (ref "R35") (pin "1") (pinfunction "1_1") (pintype "passive"))
      (node (ref "R36") (pin "1") (pinfunction "1_1") (pintype "passive"))
      (node (ref "R37") (pin "1") (pinfunction "1_1") (pintype "passive"))
      (node (ref "R47") (pin "1") (pinfunction "1_1") (pintype "passive"))
      (node (ref "R50") (pin "1") (pinfunction "1_1") (pintype "passive"))
      (node (ref "R52") (pin "1") (pinfunction "1_1") (pintype "passive"))
      (node (ref "R54") (pin "1") (pinfunction "1_1") (pintype "passive"))
      (node (ref "U2") (pin "1") (pinfunction "VBAT_1") (pintype "power_in"))
      (node (ref "U2") (pin "13") (pinfunction "VDDA/VREF+_13") (pintype "power_in"))
      (node (ref "U2") (pin "19") (pinfunction "VDD_2_19") (pintype "power_in"))
      (node (ref "U2") (pin "32") (pinfunction "VDD_3_32") (pintype "power_in"))
      (node (ref "U2") (pin "48") (pinfunction "VDD_4_48") (pintype "power_in"))
      (node (ref "U2") (pin "64") (pinfunction "VDD_64") (pintype "power_in"))
      (node (ref "X3") (pin "P1") (pinfunction "1_P1") (pintype "bidirectional"))
    )
    (net (code "2") (name "+5V") (class "Default")
      (node (ref "ADC1") (pin "15") (pinfunction "AVDD_15") (pintype "power_in"))
      (node (ref "C10") (pin "1") (pinfunction "1_1") (pintype "passive"))
      (node (ref "C11") (pin "1") (pinfunction "1_1") (pintype "passive"))
      (node (ref "C12") (pin "1") (pinfunction "1_1") (pintype "passive"))
      (node (ref "C20") (pin "1") (pinfunction "1_1") (pintype "passive"))
      (node (ref "C25") (pin "1") (pinfunction "1_1") (pintype "passive"))
      (node (ref "C49") (pin "1") (pinfunction "1_1") (pintype "passive"))
      (node (ref "C8") (pin "1") (pinfunction "1_1") (pintype "passive"))
      (node (ref "D1") (pin "2") (pinfunction "C2_2") (pintype "passive"))
      (node (ref "D2") (pin "2") (pinfunction "C2_2") (pintype "passive"))
      (node (ref "LDO2") (pin "5") (pinfunction "OUT_5") (pintype "power_in"))
      (node (ref "OP1") (pin "8") (pinfunction "V+_8") (pintype "power_in"))
      (node (ref "OP2") (pin "8") (pinfunction "V+_8") (pintype "power_in"))
      (node (ref "OP3") (pin "8") (pinfunction "V+_8") (pintype "power_in"))
      (node (ref "OP4") (pin "8") (pinfunction "V+_8") (pintype "power_in"))
      (node (ref "U1") (pin "4") (pinfunction "VIN_4") (pintype "power_in"))
    )
    (net (code "3") (name "+5V_IN") (class "Default")
      (node (ref "C2") (pin "1") (pinfunction "1_1") (pintype "passive"))
      (node (ref "C47") (pin "1") (pinfunction "1_1") (pintype "passive"))
      (node (ref "DC-DC_3V3") (pin "7") (pinfunction "+VOUT_7") (pintype "bidirectional"))
      (node (ref "LDO1") (pin "1") (pinfunction "IN_1") (pintype "input"))
      (node (ref "LDO1") (pin "3") (pinfunction "EN_3") (pintype "input"))
      (node (ref "R83") (pin "1") (pinfunction "1_1") (pintype "passive"))
    )
    (net (code "4") (name "+5V_USB") (class "Default")
      (node (ref "C39") (pin "1") (pinfunction "1_1") (pintype "passive"))
      (node (ref "C44") (pin "1") (pinfunction "1_1") (pintype "passive"))
      (node (ref "C52") (pin "1") (pinfunction "1_1") (pintype "passive"))
      (node (ref "DC-DC_3V3") (pin "1") (pinfunction "+VIN_1") (pintype "bidirectional"))
      (node (ref "DC-DC_9V") (pin "1") (pinfunction "+VIN_1") (pintype "bidirectional"))
      (node (ref "IC1") (pin "5") (pinfunction "VBUS_5") (pintype "bidirectional"))
      (node (ref "ISO_1") (pin "1") (pinfunction "VBUS1_1") (pintype "power_in"))
      (node (ref "USB1") (pin "1") (pinfunction "VBUS_1") (pintype "passive"))
      (node (ref "X4") (pin "2") (pinfunction "S_2") (pintype "passive"))
    )
    (net (code "5") (name "+9V") (class "Default")
      (node (ref "C43") (pin "1") (pinfunction "1_1") (pintype "passive"))
      (node (ref "C50") (pin "1") (pinfunction "1_1") (pintype "passive"))
      (node (ref "DC-DC_9V") (pin "6") (pinfunction "+VOUT_6") (pintype "bidirectional"))
      (node (ref "LDO2") (pin "1") (pinfunction "IN_1") (pintype "input"))
      (node (ref "LDO2") (pin "3") (pinfunction "EN_3") (pintype "input"))
      (node (ref "R111") (pin "1") (pinfunction "1_1") (pintype "passive"))
    )
    (net (code "6") (name "-5V") (class "Default")
      (node (ref "C13") (pin "2") (pinfunction "2_2") (pintype "passive"))
      (node (ref "C14") (pin "2") (pinfunction "2_2") (pintype "passive"))
      (node (ref "C15") (pin "2") (pinfunction "2_2") (pintype "passive"))
      (node (ref "C16") (pin "2") (pinfunction "2_2") (pintype "passive"))
      (node (ref "C65") (pin "1") (pinfunction "1_1") (pintype "passive"))
      (node (ref "D1") (pin "1") (pinfunction "A1_1") (pintype "passive"))
      (node (ref "D2") (pin "1") (pinfunction "A1_1") (pintype "passive"))
      (node (ref "LDO3") (pin "4") (pinfunction "OUT_4") (pintype "power_in"))
      (node (ref "OP1") (pin "4") (pinfunction "V-_4") (pintype "power_in"))
      (node (ref "OP2") (pin "4") (pinfunction "V-_4") (pintype "power_in"))
      (node (ref "OP3") (pin "4") (pinfunction "V-_4") (pintype "power_in"))
      (node (ref "OP4") (pin "4") (pinfunction "V-_4") (pintype "power_in"))
    )
    (net (code "7") (name "-9V") (class "Default")
      (node (ref "C51") (pin "2") (pinfunction "2_2") (pintype "passive"))
      (node (ref "C66") (pin "1") (pinfunction "1_1") (pintype "passive"))
      (node (ref "DC-DC_9V") (pin "4") (pinfunction "-VOUT_4") (pintype "bidirectional"))
      (node (ref "LDO3") (pin "5") (pinfunction "IN_5") (pintype "input"))
      (node (ref "R15") (pin "2") (pinfunction "2_2") (pintype "passive"))
    )
    (net (code "8") (name "ADC_CONVERSION") (class "Default")
      (node (ref "ADC1") (pin "5") (pinfunction "~{CONVST}_5") (pintype "input"))
      (node (ref "SJ2") (pin "2") (pinfunction "2_2") (pintype "passive"))
    )
    (net (code "9") (name "ADC_SCK") (class "Default")
      (node (ref "ADC1") (pin "10") (pinfunction "SCLK_10") (pintype "input"))
      (node (ref "R28") (pin "2") (pinfunction "2_2") (pintype "passive"))
    )
    (net (code "10") (name "ADC_SDO_I") (class "Default")
      (node (ref "ADC1") (pin "7") (pinfunction "DOUT1_7") (pintype "output"))
      (node (ref "R24") (pin "2") (pinfunction "2_2") (pintype "passive"))
    )
    (net (code "11") (name "ADC_SDO_V") (class "Default")
      (node (ref "ADC1") (pin "8") (pinfunction "DOUT2_8") (pintype "output"))
      (node (ref "SJ1") (pin "2") (pinfunction "2_2") (pintype "passive"))
    )
    (net (code "12") (name "AGND") (class "Default")
      (node (ref "ADC1") (pin "12") (pinfunction "REFGND_12") (pintype "passive"))
      (node (ref "ADC1") (pin "16") (pinfunction "AGND_16") (pintype "passive"))
      (node (ref "ADC1") (pin "EXP") (pinfunction "AGND_EXP") (pintype "passive"))
      (node (ref "C10") (pin "2") (pinfunction "2_2") (pintype "passive"))
      (node (ref "C11") (pin "2") (pinfunction "2_2") (pintype "passive"))
      (node (ref "C12") (pin "2") (pinfunction "2_2") (pintype "passive"))
      (node (ref "C13") (pin "1") (pinfunction "1_1") (pintype "passive"))
      (node (ref "C14") (pin "1") (pinfunction "1_1") (pintype "passive"))
      (node (ref "C15") (pin "1") (pinfunction "1_1") (pintype "passive"))
      (node (ref "C16") (pin "1") (pinfunction "1_1") (pintype "passive"))
      (node (ref "C20") (pin "2") (pinfunction "2_2") (pintype "passive"))
      (node (ref "C25") (pin "2") (pinfunction "2_2") (pintype "passive"))
      (node (ref "C26") (pin "2") (pinfunction "2_2") (pintype "passive"))
      (node (ref "C27") (pin "2") (pinfunction "2_2") (pintype "passive"))
      (node (ref "C37") (pin "2") (pinfunction "2_2") (pintype "passive"))
      (node (ref "C38") (pin "1") (pinfunction "1_1") (pintype "passive"))
      (node (ref "C43") (pin "2") (pinfunction "2_2") (pintype "passive"))
      (node (ref "C45") (pin "2") (pinfunction "2_2") (pintype "passive"))
      (node (ref "C46") (pin "1") (pinfunction "1_1") (pintype "passive"))
      (node (ref "C49") (pin "2") (pinfunction "2_2") (pintype "passive"))
      (node (ref "C50") (pin "2") (pinfunction "2_2") (pintype "passive"))
      (node (ref "C51") (pin "1") (pinfunction "1_1") (pintype "passive"))
      (node (ref "C60") (pin "2") (pinfunction "2_2") (pintype "passive"))
      (node (ref "C61") (pin "2") (pinfunction "2_2") (pintype "passive"))
      (node (ref "C65") (pin "2") (pinfunction "2_2") (pintype "passive"))
      (node (ref "C66") (pin "2") (pinfunction "2_2") (pintype "passive"))
      (node (ref "C8") (pin "2") (pinfunction "2_2") (pintype "passive"))
      (node (ref "DC-DC_9V") (pin "5") (pinfunction "0V_5") (pintype "bidirectional"))
      (node (ref "LDO2") (pin "2") (pinfunction "GND_2") (pintype "passive"))
      (node (ref "LDO3") (pin "2") (pinfunction "GND_2") (pintype "passive"))
      (node (ref "LED1") (pin "C") (pinfunction "C_C") (pintype "passive"))
      (node (ref "LED2") (pin "A") (pinfunction "A_A") (pintype "passive"))
      (node (ref "R107") (pin "2") (pinfunction "2_2") (pintype "passive"))
      (node (ref "R23") (pin "2") (pinfunction "2_2") (pintype "passive"))
      (node (ref "R2V_ADJ") (pin "2") (pinfunction "2_2") (pintype "passive"))
      (node (ref "R38") (pin "2") (pinfunction "2_2") (pintype "passive"))
      (node (ref "R89") (pin "2") (pinfunction "2_2") (pintype "passive"))
      (node (ref "R9") (pin "2") (pinfunction "2_2") (pintype "passive"))
      (node (ref "R91") (pin "2") (pinfunction "2_2") (pintype "passive"))
      (node (ref "U1") (pin "1") (pinfunction "GND_2_1") (pintype "passive"))
      (node (ref "U1") (pin "2") (pinfunction "GND_2") (pintype "passive"))
    )
    (net (code "13") (name "AIN1+") (class "Default")
      (node (ref "ADC1") (pin "4") (pinfunction "AIN2-_4") (pintype "bidirectional"))
      (node (ref "C1") (pin "2") (pinfunction "2_2") (pintype "passive"))
      (node (ref "C38") (pin "2") (pinfunction "2_2") (pintype "passive"))
      (node (ref "R3") (pin "1") (pinfunction "1_1") (pintype "passive"))
    )
    (net (code "14") (name "AIN1-") (class "Default")
      (node (ref "ADC1") (pin "3") (pinfunction "AIN2+_3") (pintype "bidirectional"))
      (node (ref "C1") (pin "1") (pinfunction "1_1") (pintype "passive"))
      (node (ref "C37") (pin "1") (pinfunction "1_1") (pintype "passive"))
      (node (ref "R6") (pin "2") (pinfunction "2_2") (pintype "passive"))
    )
    (net (code "15") (name "AIN2+") (class "Default")
      (node (ref "ADC1") (pin "2") (pinfunction "AIN1-_2") (pintype "bidirectional"))
      (node (ref "C42") (pin "1") (pinfunction "1_1") (pintype "passive"))
      (node (ref "C45") (pin "1") (pinfunction "1_1") (pintype "passive"))
      (node (ref "R104") (pin "2") (pinfunction "2_2") (pintype "passive"))
    )
    (net (code "16") (name "AIN2-") (class "Default")
      (node (ref "ADC1") (pin "1") (pinfunction "AIN1+_1") (pintype "bidirectional"))
      (node (ref "C42") (pin "2") (pinfunction "2_2") (pintype "passive"))
      (node (ref "C46") (pin "2") (pinfunction "2_2") (pintype "passive"))
      (node (ref "R85") (pin "1") (pinfunction "1_1") (pintype "passive"))
    )
    (net (code "17") (name "DEBUG1") (class "Default")
      (node (ref "R40") (pin "1") (pinfunction "1_1") (pintype "passive"))
      (node (ref "U2") (pin "54") (pinfunction "PD2_54") (pintype "bidirectional"))
      (node (ref "X2") (pin "P2") (pinfunction "2_P2") (pintype "bidirectional"))
    )
    (net (code "18") (name "DEBUG2") (class "Default")
      (node (ref "U2") (pin "53") (pinfunction "PC12_53") (pintype "bidirectional"))
      (node (ref "X2") (pin "P1") (pinfunction "1_P1") (pintype "bidirectional"))
    )
    (net (code "19") (name "DEBUG3") (class "Default")
      (node (ref "U2") (pin "50") (pinfunction "PA15_50") (pintype "bidirectional"))
      (node (ref "X2") (pin "P5") (pinfunction "5_P5") (pintype "bidirectional"))
    )
    (net (code "20") (name "DETECT_DEMUX_N1") (class "Default")
      (node (ref "J1") (pin "5") (pinfunction "S_5") (pintype "passive"))
      (node (ref "U2") (pin "20") (pinfunction "PA4_20") (pintype "bidirectional"))
    )
    (net (code "21") (name "DETECT_DEMUX_N2") (class "Default")
      (node (ref "J1") (pin "6") (pinfunction "S_6") (pintype "passive"))
      (node (ref "U2") (pin "16") (pinfunction "PA2_16") (pintype "bidirectional"))
    )
    (net (code "22") (name "DETECT_DEMUX_N3") (class "Default")
      (node (ref "J1") (pin "7") (pinfunction "S_7") (pintype "passive"))
      (node (ref "U2") (pin "11") (pinfunction "PC3_11") (pintype "bidirectional"))
    )
    (net (code "23") (name "DETECT_DEMUX_N4") (class "Default")
      (node (ref "J1") (pin "8") (pinfunction "S_8") (pintype "passive"))
      (node (ref "U2") (pin "10") (pinfunction "PC2_10") (pintype "bidirectional"))
    )
    (net (code "24") (name "DETECT_DEMUX_P1") (class "Default")
      (node (ref "J3") (pin "7") (pinfunction "S_7") (pintype "passive"))
      (node (ref "U2") (pin "35") (pinfunction "PB14_35") (pintype "bidirectional"))
    )
    (net (code "25") (name "DETECT_DEMUX_P2") (class "Default")
      (node (ref "J3") (pin "8") (pinfunction "S_8") (pintype "passive"))
      (node (ref "U2") (pin "36") (pinfunction "PB15_36") (pintype "bidirectional"))
    )
    (net (code "26") (name "DETECT_DEMUX_P3") (class "Default")
      (node (ref "J3") (pin "9") (pinfunction "S_9") (pintype "passive"))
      (node (ref "U2") (pin "37") (pinfunction "PC6_37") (pintype "bidirectional"))
    )
    (net (code "27") (name "DETECT_DEMUX_P4") (class "Default")
      (node (ref "J3") (pin "10") (pinfunction "S_10") (pintype "passive"))
      (node (ref "U2") (pin "38") (pinfunction "PC7_38") (pintype "bidirectional"))
    )
    (net (code "28") (name "GND") (class "Default")
      (node (ref "ADC1") (pin "6") (pinfunction "OGND_6") (pintype "passive"))
      (node (ref "C2") (pin "2") (pinfunction "2_2") (pintype "passive"))
      (node (ref "C21") (pin "2") (pinfunction "2_2") (pintype "passive"))
      (node (ref "C22") (pin "2") (pinfunction "2_2") (pintype "passive"))
      (node (ref "C23") (pin "2") (pinfunction "2_2") (pintype "passive"))
      (node (ref "C24") (pin "2") (pinfunction "2_2") (pintype "passive"))
      (node (ref "C28") (pin "2") (pinfunction "2_2") (pintype "passive"))
      (node (ref "C29") (pin "2") (pinfunction "2_2") (pintype "passive"))
      (node (ref "C30") (pin "2") (pinfunction "2_2") (pintype "passive"))
      (node (ref "C31") (pin "2") (pinfunction "2_2") (pintype "passive"))
      (node (ref "C32") (pin "2") (pinfunction "2_2") (pintype "passive"))
      (node (ref "C33") (pin "2") (pinfunction "2_2") (pintype "passive"))
      (node (ref "C34") (pin "2") (pinfunction "2_2") (pintype "passive"))
      (node (ref "C35") (pin "2") (pinfunction "2_2") (pintype "passive"))
      (node (ref "C36") (pin "2") (pinfunction "2_2") (pintype "passive"))
      (node (ref "C4") (pin "2") (pinfunction "2_2") (pintype "passive"))
      (node (ref "C41") (pin "2") (pinfunction "2_2") (pintype "passive"))
      (node (ref "C47") (pin "2") (pinfunction "2_2") (pintype "passive"))
      (node (ref "C5") (pin "2") (pinfunction "2_2") (pintype "passive"))
      (node (ref "C6") (pin "2") (pinfunction "2_2") (pintype "passive"))
      (node (ref "C67") (pin "2") (pinfunction "2_2") (pintype "passive"))
      (node (ref "C68") (pin "2") (pinfunction "2_2") (pintype "passive"))
      (node (ref "C7") (pin "2") (pinfunction "2_2") (pintype "passive"))
      (node (ref "C9") (pin "2") (pinfunction "2_2") (pintype "passive"))
      (node (ref "COMP1") (pin "4") (pinfunction "V-_4") (pintype "power_in"))
      (node (ref "COMP3") (pin "4") (pinfunction "V-_4") (pintype "power_in"))
      (node (ref "DC-DC_3V3") (pin "5") (pinfunction "-VOUT_5") (pintype "bidirectional"))
      (node (ref "ISO_1") (pin "15") (pinfunction "GND2_15") (pintype "power_in"))
      (node (ref "ISO_1") (pin "9") (pinfunction "GND2_9") (pintype "power_in"))
      (node (ref "J1") (pin "4") (pinfunction "S_4") (pintype "passive"))
      (node (ref "J3") (pin "6") (pinfunction "S_6") (pintype "passive"))
      (node (ref "LDO1") (pin "2") (pinfunction "GND_2") (pintype "passive"))
      (node (ref "LED3") (pin "C") (pinfunction "C_C") (pintype "passive"))
      (node (ref "LED4") (pin "C") (pinfunction "C_C") (pintype "passive"))
      (node (ref "LED6") (pin "C") (pinfunction "C_C") (pintype "passive"))
      (node (ref "OK21") (pin "5") (pinfunction "GND_5") (pintype "power_in"))
      (node (ref "OK22") (pin "5") (pinfunction "GND_5") (pintype "power_in"))
      (node (ref "OK23") (pin "5") (pinfunction "GND_5") (pintype "power_in"))
      (node (ref "OK24") (pin "5") (pinfunction "GND_5") (pintype "power_in"))
      (node (ref "OK4") (pin "5") (pinfunction "GND_5") (pintype "power_in"))
      (node (ref "OK6") (pin "5") (pinfunction "GND_5") (pintype "power_in"))
      (node (ref "OK7") (pin "5") (pinfunction "GND_5") (pintype "power_in"))
      (node (ref "OK9") (pin "5") (pinfunction "GND_5") (pintype "power_in"))
      (node (ref "OSC1") (pin "2") (pinfunction "GND_2") (pintype "power_in"))
      (node (ref "R27") (pin "1") (pinfunction "1_1") (pintype "passive"))
      (node (ref "R29") (pin "1") (pinfunction "1_1") (pintype "passive"))
      (node (ref "R2COMP1_ADJ") (pin "1") (pinfunction "1_1") (pintype "passive"))
      (node (ref "R2COMP1_ADJ1") (pin "1") (pinfunction "1_1") (pintype "passive"))
      (node (ref "R2COMP2_ADJ") (pin "1") (pinfunction "1_1") (pintype "passive"))
      (node (ref "R2COMP2_ADJ1") (pin "1") (pinfunction "1_1") (pintype "passive"))
      (node (ref "R30") (pin "1") (pinfunction "1_1") (pintype "passive"))
      (node (ref "R38") (pin "1") (pinfunction "1_1") (pintype "passive"))
      (node (ref "R87") (pin "1") (pinfunction "1_1") (pintype "passive"))
      (node (ref "S1") (pin "4") (pinfunction "4_4") (pintype "passive"))
      (node (ref "U2") (pin "12") (pinfunction "VSSA/VREF-_12") (pintype "power_in"))
      (node (ref "U2") (pin "18") (pinfunction "VSS_2_18") (pintype "power_in"))
      (node (ref "U2") (pin "31") (pinfunction "VSS_3_31") (pintype "power_in"))
      (node (ref "U2") (pin "47") (pinfunction "VSS_4_47") (pintype "power_in"))
      (node (ref "U2") (pin "60") (pinfunction "BOOT0_60") (pintype "input"))
      (node (ref "U2") (pin "63") (pinfunction "VSS_63") (pintype "power_in"))
      (node (ref "X2") (pin "P6") (pinfunction "6_P6") (pintype "bidirectional"))
      (node (ref "X3") (pin "P3") (pinfunction "3_P3") (pintype "bidirectional"))
    )
    (net (code "29") (name "GND_USB") (class "Default")
      (node (ref "C39") (pin "2") (pinfunction "2_2") (pintype "passive"))
      (node (ref "C40") (pin "2") (pinfunction "2_2") (pintype "passive"))
      (node (ref "C44") (pin "2") (pinfunction "2_2") (pintype "passive"))
      (node (ref "C52") (pin "2") (pinfunction "2_2") (pintype "passive"))
      (node (ref "DC-DC_3V3") (pin "2") (pinfunction "-VIN_2") (pintype "bidirectional"))
      (node (ref "DC-DC_9V") (pin "2") (pinfunction "GND_2") (pintype "bidirectional"))
      (node (ref "IC1") (pin "2") (pinfunction "GND_2") (pintype "bidirectional"))
      (node (ref "ISO_1") (pin "2") (pinfunction "GND1_2") (pintype "power_in"))
      (node (ref "ISO_1") (pin "8") (pinfunction "GND1_8") (pintype "power_in"))
      (node (ref "R81") (pin "1") (pinfunction "1_1") (pintype "passive"))
      (node (ref "USB1") (pin "5") (pinfunction "GND_5") (pintype "passive"))
      (node (ref "X4") (pin "1") (pinfunction "S_1") (pintype "passive"))
    )
    (net (code "30") (name "I2C1_SCL") (class "Default")
      (node (ref "J3") (pin "11") (pinfunction "S_11") (pintype "passive"))
      (node (ref "R34") (pin "2") (pinfunction "2_2") (pintype "passive"))
      (node (ref "U2") (pin "58") (pinfunction "PB6_58") (pintype "bidirectional"))
    )
    (net (code "31") (name "I2C1_SDA") (class "Default")
      (node (ref "J3") (pin "12") (pinfunction "S_12") (pintype "passive"))
      (node (ref "R35") (pin "2") (pinfunction "2_2") (pintype "passive"))
      (node (ref "U2") (pin "59") (pinfunction "PB7_59") (pintype "bidirectional"))
    )
    (net (code "32") (name "I2C2_SCL") (class "Default")
      (node (ref "J1") (pin "9") (pinfunction "S_9") (pintype "passive"))
      (node (ref "R32") (pin "2") (pinfunction "2_2") (pintype "passive"))
      (node (ref "U2") (pin "29") (pinfunction "PB10_29") (pintype "bidirectional"))
    )
    (net (code "33") (name "I2C2_SDA") (class "Default")
      (node (ref "J1") (pin "10") (pinfunction "S_10") (pintype "passive"))
      (node (ref "R33") (pin "2") (pinfunction "2_2") (pintype "passive"))
      (node (ref "U2") (pin "62") (pinfunction "PB9_62") (pintype "bidirectional"))
    )
    (net (code "34") (name "I2C3_SCL") (class "Default")
      (node (ref "J3") (pin "1") (pinfunction "S_1") (pintype "passive"))
      (node (ref "R36") (pin "2") (pinfunction "2_2") (pintype "passive"))
      (node (ref "U2") (pin "41") (pinfunction "PA8_41") (pintype "bidirectional"))
    )
    (net (code "35") (name "I2C3_SDA") (class "Default")
      (node (ref "J3") (pin "2") (pinfunction "S_2") (pintype "passive"))
      (node (ref "R37") (pin "2") (pinfunction "2_2") (pintype "passive"))
      (node (ref "U2") (pin "56") (pinfunction "PB4_56") (pintype "bidirectional"))
    )
    (net (code "36") (name "I_MESS") (class "Default")
      (node (ref "D1") (pin "3") (pinfunction "C1A2_3") (pintype "passive"))
      (node (ref "OP1") (pin "3") (pinfunction "IN+_3") (pintype "input"))
      (node (ref "SJ7") (pin "2") (pinfunction "2_2") (pintype "passive"))
    )
    (net (code "37") (name "LED1") (class "Default")
      (node (ref "R79") (pin "1") (pinfunction "1_1") (pintype "passive"))
      (node (ref "U2") (pin "61") (pinfunction "PB8_61") (pintype "bidirectional"))
    )
    (net (code "38") (name "LED2") (class "Default")
      (node (ref "R31") (pin "1") (pinfunction "1_1") (pintype "passive"))
      (node (ref "U2") (pin "57") (pinfunction "PB5_57") (pintype "bidirectional"))
    )
    (net (code "39") (name "MCLK2_OUT") (class "Default")
      (node (ref "SJ2") (pin "1") (pinfunction "1_1") (pintype "passive"))
      (node (ref "U2") (pin "40") (pinfunction "PC9_40") (pintype "bidirectional"))
    )
    (net (code "40") (name "NPULSE_DETECT_I") (class "Default")
      (node (ref "COMP3") (pin "7") (pinfunction "OUT_7") (pintype "output"))
      (node (ref "G17") (pin "A") (pinfunction "A_A") (pintype "passive"))
      (node (ref "U2") (pin "28") (pinfunction "PB2_28") (pintype "bidirectional"))
    )
    (net (code "41") (name "NPULSE_DETECT_V") (class "Default")
      (node (ref "COMP1") (pin "7") (pinfunction "OUT_7") (pintype "output"))
      (node (ref "G18") (pin "A") (pinfunction "A_A") (pintype "passive"))
      (node (ref "U2") (pin "17") (pinfunction "PA3_17") (pintype "bidirectional"))
    )
    (net (code "42") (name "Net-(ADC1-REF1)") (class "Default")
      (node (ref "ADC1") (pin "13") (pinfunction "REF1_13") (pintype "bidirectional"))
      (node (ref "C26") (pin "1") (pinfunction "1_1") (pintype "passive"))
    )
    (net (code "43") (name "Net-(ADC1-REF2)") (class "Default")
      (node (ref "ADC1") (pin "11") (pinfunction "REF2_11") (pintype "bidirectional"))
      (node (ref "C27") (pin "1") (pinfunction "1_1") (pintype "passive"))
    )
    (net (code "44") (name "Net-(C17-Pad1)") (class "Default")
      (node (ref "C17") (pin "1") (pinfunction "1_1") (pintype "passive"))
      (node (ref "JP8") (pin "2") (pinfunction "2_2") (pintype "passive"))
      (node (ref "R19") (pin "2") (pinfunction "2_2") (pintype "passive"))
    )
    (net (code "45") (name "Net-(C17-Pad2)") (class "Default")
      (node (ref "C17") (pin "2") (pinfunction "2_2") (pintype "passive"))
      (node (ref "R19") (pin "1") (pinfunction "1_1") (pintype "passive"))
      (node (ref "R2") (pin "1") (pinfunction "1_1") (pintype "passive"))
    )
    (net (code "46") (name "Net-(C18-Pad1)") (class "Default")
      (node (ref "C18") (pin "1") (pinfunction "1_1") (pintype "passive"))
      (node (ref "R20") (pin "2") (pinfunction "2_2") (pintype "passive"))
      (node (ref "R21") (pin "1") (pinfunction "1_1") (pintype "passive"))
    )
    (net (code "47") (name "Net-(C18-Pad2)") (class "Default")
      (node (ref "C18") (pin "2") (pinfunction "2_2") (pintype "passive"))
      (node (ref "JP5") (pin "2") (pinfunction "2_2") (pintype "passive"))
      (node (ref "R20") (pin "1") (pinfunction "1_1") (pintype "passive"))
    )
    (net (code "48") (name "Net-(C19-Pad1)") (class "Default")
      (node (ref "C19") (pin "1") (pinfunction "1_1") (pintype "passive"))
      (node (ref "JP6") (pin "2") (pinfunction "2_2") (pintype "passive"))
      (node (ref "R22") (pin "2") (pinfunction "2_2") (pintype "passive"))
    )
    (net (code "49") (name "Net-(C19-Pad2)") (class "Default")
      (node (ref "C19") (pin "2") (pinfunction "2_2") (pintype "passive"))
      (node (ref "R21") (pin "2") (pinfunction "2_2") (pintype "passive"))
      (node (ref "R22") (pin "1") (pinfunction "1_1") (pintype "passive"))
    )
    (net (code "50") (name "Net-(C68-Pad1)") (class "Default")
      (node (ref "C68") (pin "1") (pinfunction "1_1") (pintype "passive"))
      (node (ref "R14") (pin "1") (pinfunction "1_1") (pintype "passive"))
      (node (ref "R39") (pin "2") (pinfunction "2_2") (pintype "passive"))
      (node (ref "R40") (pin "2") (pinfunction "2_2") (pintype "passive"))
      (node (ref "S1") (pin "2") (pinfunction "2_2") (pintype "passive"))
    )
    (net (code "51") (name "Net-(CH_A_BRAUN-P)") (class "Default")
      (node (ref "CH_A_BRAUN") (pin "1") (pinfunction "P_1") (pintype "passive"))
      (node (ref "JP1") (pin "2") (pinfunction "2_2") (pintype "passive"))
      (node (ref "STIM_LOAD_OUT_P") (pin "1") (pinfunction "P_1") (pintype "passive"))
    )
    (net (code "52") (name "Net-(CH_A_WEISS-P)") (class "Default")
      (node (ref "CH_A_WEISS") (pin "1") (pinfunction "P_1") (pintype "passive"))
      (node (ref "JP2") (pin "2") (pinfunction "2_2") (pintype "passive"))
      (node (ref "STIM_LOAD_OUT_N") (pin "1") (pinfunction "P_1") (pintype "passive"))
    )
    (net (code "53") (name "Net-(COMP1A--IN)") (class "Default")
      (node (ref "COMP1") (pin "2") (pinfunction "-IN_2") (pintype "input"))
      (node (ref "R1COMP3") (pin "2") (pinfunction "2_2") (pintype "passive"))
      (node (ref "R2COMP3") (pin "1") (pinfunction "1_1") (pintype "passive"))
    )
    (net (code "54") (name "Net-(COMP1B-+IN)") (class "Default")
      (node (ref "COMP1") (pin "5") (pinfunction "+IN_5") (pintype "input"))
      (node (ref "R1COMP4") (pin "2") (pinfunction "2_2") (pintype "passive"))
      (node (ref "R2COMP4") (pin "1") (pinfunction "1_1") (pintype "passive"))
    )
    (net (code "55") (name "Net-(COMP3A-+IN)") (class "Default")
      (node (ref "COMP3") (pin "3") (pinfunction "+IN_3") (pintype "input"))
      (node (ref "COMP3") (pin "6") (pinfunction "-IN_6") (pintype "input"))
      (node (ref "OP2") (pin "1") (pinfunction "OUT_1") (pintype "output"))
      (node (ref "OP2") (pin "2") (pinfunction "IN-_2") (pintype "input"))
    )
    (net (code "56") (name "Net-(COMP3A--IN)") (class "Default")
      (node (ref "COMP3") (pin "2") (pinfunction "-IN_2") (pintype "input"))
      (node (ref "R1COMP1") (pin "2") (pinfunction "2_2") (pintype "passive"))
      (node (ref "R2COMP1") (pin "1") (pinfunction "1_1") (pintype "passive"))
    )
    (net (code "57") (name "Net-(COMP3B-+IN)") (class "Default")
      (node (ref "COMP3") (pin "5") (pinfunction "+IN_5") (pintype "input"))
      (node (ref "R1COMP2") (pin "2") (pinfunction "2_2") (pintype "passive"))
      (node (ref "R2COMP2") (pin "1") (pinfunction "1_1") (pintype "passive"))
    )
    (net (code "58") (name "Net-(G17-PadC)") (class "Default")
      (node (ref "G17") (pin "C") (pinfunction "C_C") (pintype "passive"))
      (node (ref "R87") (pin "2") (pinfunction "2_2") (pintype "passive"))
    )
    (net (code "59") (name "Net-(G18-PadC)") (class "Default")
      (node (ref "G18") (pin "C") (pinfunction "C_C") (pintype "passive"))
      (node (ref "R30") (pin "2") (pinfunction "2_2") (pintype "passive"))
    )
    (net (code "60") (name "Net-(IC1-IO1-Pad6)") (class "Default")
      (node (ref "IC1") (pin "6") (pinfunction "IO1_6") (pintype "bidirectional"))
      (node (ref "R48") (pin "1") (pinfunction "1_1") (pintype "passive"))
    )
    (net (code "61") (name "Net-(IC1-IO2-Pad4)") (class "Default")
      (node (ref "IC1") (pin "4") (pinfunction "IO2_4") (pintype "bidirectional"))
      (node (ref "R80") (pin "1") (pinfunction "1_1") (pintype "passive"))
    )
    (net (code "62") (name "Net-(ISO_1-PDEN)") (class "Default")
      (node (ref "C40") (pin "1") (pinfunction "1_1") (pintype "passive"))
      (node (ref "ISO_1") (pin "3") (pinfunction "VDD1_3") (pintype "power_in"))
      (node (ref "ISO_1") (pin "4") (pinfunction "PDEN_4") (pintype "input"))
      (node (ref "ISO_1") (pin "5") (pinfunction "SPU_5") (pintype "input"))
    )
    (net (code "63") (name "Net-(ISO_1-UD+)") (class "Default")
      (node (ref "ISO_1") (pin "7") (pinfunction "UD+_7") (pintype "bidirectional"))
      (node (ref "R80") (pin "2") (pinfunction "2_2") (pintype "passive"))
    )
    (net (code "64") (name "Net-(ISO_1-UD-)") (class "Default")
      (node (ref "ISO_1") (pin "6") (pinfunction "UD-_6") (pintype "bidirectional"))
      (node (ref "R48") (pin "2") (pinfunction "2_2") (pintype "passive"))
    )
    (net (code "65") (name "Net-(JP1-Pad1)") (class "Default")
      (node (ref "JP1") (pin "1") (pinfunction "1_1") (pintype "passive"))
      (node (ref "JP3") (pin "1") (pinfunction "1_1") (pintype "passive"))
      (node (ref "JP5") (pin "1") (pinfunction "1_1") (pintype "passive"))
      (node (ref "JP7") (pin "1") (pinfunction "1_1") (pintype "passive"))
      (node (ref "JP9") (pin "1") (pinfunction "1_1") (pintype "passive"))
      (node (ref "R89") (pin "1") (pinfunction "1_1") (pintype "passive"))
      (node (ref "R_MESS") (pin "1") (pinfunction "1_1") (pintype "passive"))
      (node (ref "R_MESS_ADJ") (pin "2") (pinfunction "2_2") (pintype "passive"))
      (node (ref "SJ7") (pin "1") (pinfunction "1_1") (pintype "passive"))
    )
    (net (code "66") (name "Net-(JP7-Pad2)") (class "Default")
      (node (ref "JP7") (pin "2") (pinfunction "2_2") (pintype "passive"))
      (node (ref "R2") (pin "2") (pinfunction "2_2") (pintype "passive"))
    )
    (net (code "67") (name "Net-(JP9-Pad2)") (class "Default")
      (node (ref "JP9") (pin "2") (pinfunction "2_2") (pintype "passive"))
      (node (ref "R1") (pin "1") (pinfunction "1_1") (pintype "passive"))
    )
    (net (code "68") (name "Net-(JP10-Pad2)") (class "Default")
      (node (ref "JP10") (pin "2") (pinfunction "2_2") (pintype "passive"))
      (node (ref "R1") (pin "2") (pinfunction "2_2") (pintype "passive"))
    )
    (net (code "69") (name "Net-(LED1-PadA)") (class "Default")
      (node (ref "LED1") (pin "A") (pinfunction "A_A") (pintype "passive"))
      (node (ref "R111") (pin "2") (pinfunction "2_2") (pintype "passive"))
    )
    (net (code "70") (name "Net-(LED2-PadC)") (class "Default")
      (node (ref "LED2") (pin "C") (pinfunction "C_C") (pintype "passive"))
      (node (ref "R15") (pin "1") (pinfunction "1_1") (pintype "passive"))
    )
    (net (code "71") (name "Net-(LED3-PadA)") (class "Default")
      (node (ref "LED3") (pin "A") (pinfunction "A_A") (pintype "passive"))
      (node (ref "R83") (pin "2") (pinfunction "2_2") (pintype "passive"))
    )
    (net (code "72") (name "Net-(LED4-PadA)") (class "Default")
      (node (ref "LED4") (pin "A") (pinfunction "A_A") (pintype "passive"))
      (node (ref "R31") (pin "2") (pinfunction "2_2") (pintype "passive"))
    )
    (net (code "73") (name "Net-(LED6-PadA)") (class "Default")
      (node (ref "LED6") (pin "A") (pinfunction "A_A") (pintype "passive"))
      (node (ref "R79") (pin "2") (pinfunction "2_2") (pintype "passive"))
    )
    (net (code "74") (name "Net-(OK4-A)") (class "Default")
      (node (ref "OK4") (pin "1") (pinfunction "A_1") (pintype "passive"))
      (node (ref "R11") (pin "1") (pinfunction "1_1") (pintype "passive"))
    )
    (net (code "75") (name "Net-(OK6-A)") (class "Default")
      (node (ref "OK6") (pin "1") (pinfunction "A_1") (pintype "passive"))
      (node (ref "R13") (pin "1") (pinfunction "1_1") (pintype "passive"))
    )
    (net (code "76") (name "Net-(OK7-A)") (class "Default")
      (node (ref "OK7") (pin "1") (pinfunction "A_1") (pintype "passive"))
      (node (ref "R17") (pin "1") (pinfunction "1_1") (pintype "passive"))
    )
    (net (code "77") (name "Net-(OK9-A)") (class "Default")
      (node (ref "OK9") (pin "1") (pinfunction "A_1") (pintype "passive"))
      (node (ref "R25") (pin "1") (pinfunction "1_1") (pintype "passive"))
    )
    (net (code "78") (name "Net-(OK21-A)") (class "Default")
      (node (ref "OK21") (pin "1") (pinfunction "A_1") (pintype "passive"))
      (node (ref "R46") (pin "1") (pinfunction "1_1") (pintype "passive"))
    )
    (net (code "79") (name "Net-(OK22-A)") (class "Default")
      (node (ref "OK22") (pin "1") (pinfunction "A_1") (pintype "passive"))
      (node (ref "R49") (pin "1") (pinfunction "1_1") (pintype "passive"))
    )
    (net (code "80") (name "Net-(OK23-A)") (class "Default")
      (node (ref "OK23") (pin "1") (pinfunction "A_1") (pintype "passive"))
      (node (ref "R51") (pin "1") (pinfunction "1_1") (pintype "passive"))
    )
    (net (code "81") (name "Net-(OK24-A)") (class "Default")
      (node (ref "OK24") (pin "1") (pinfunction "A_1") (pintype "passive"))
      (node (ref "R53") (pin "1") (pinfunction "1_1") (pintype "passive"))
    )
    (net (code "82") (name "Net-(OP1A-IN-)") (class "Default")
      (node (ref "OP1") (pin "1") (pinfunction "OUT_1") (pintype "output"))
      (node (ref "OP1") (pin "2") (pinfunction "IN-_2") (pintype "input"))
      (node (ref "R8") (pin "2") (pinfunction "2_2") (pintype "passive"))
    )
    (net (code "83") (name "Net-(OP1B-IN+)") (class "Default")
      (node (ref "OP1") (pin "5") (pinfunction "IN+_5") (pintype "input"))
      (node (ref "R10") (pin "1") (pinfunction "1_1") (pintype "passive"))
      (node (ref "R9") (pin "1") (pinfunction "1_1") (pintype "passive"))
    )
    (net (code "84") (name "Net-(OP1B-IN-)") (class "Default")
      (node (ref "OP1") (pin "6") (pinfunction "IN-_6") (pintype "input"))
      (node (ref "R7") (pin "2") (pinfunction "2_2") (pintype "passive"))
      (node (ref "R8") (pin "1") (pinfunction "1_1") (pintype "passive"))
    )
    (net (code "85") (name "Net-(OP2B-IN-)") (class "Default")
      (node (ref "OP2") (pin "6") (pinfunction "IN-_6") (pintype "input"))
      (node (ref "R4") (pin "2") (pinfunction "2_2") (pintype "passive"))
      (node (ref "R5") (pin "1") (pinfunction "1_1") (pintype "passive"))
    )
    (net (code "86") (name "Net-(OP3A-IN-)") (class "Default")
      (node (ref "OP3") (pin "1") (pinfunction "OUT_1") (pintype "output"))
      (node (ref "OP3") (pin "2") (pinfunction "IN-_2") (pintype "input"))
      (node (ref "R106") (pin "2") (pinfunction "2_2") (pintype "passive"))
    )
    (net (code "87") (name "Net-(OP3B-IN+)") (class "Default")
      (node (ref "OP3") (pin "5") (pinfunction "IN+_5") (pintype "input"))
      (node (ref "R107") (pin "1") (pinfunction "1_1") (pintype "passive"))
      (node (ref "R108") (pin "1") (pinfunction "1_1") (pintype "passive"))
    )
    (net (code "88") (name "Net-(OP3B-IN-)") (class "Default")
      (node (ref "OP3") (pin "6") (pinfunction "IN-_6") (pintype "input"))
      (node (ref "R105") (pin "2") (pinfunction "2_2") (pintype "passive"))
      (node (ref "R106") (pin "1") (pinfunction "1_1") (pintype "passive"))
    )
    (net (code "89") (name "Net-(OP4A-IN+)") (class "Default")
      (node (ref "OP4") (pin "3") (pinfunction "IN+_3") (pintype "input"))
      (node (ref "R84") (pin "2") (pinfunction "2_2") (pintype "passive"))
      (node (ref "R86") (pin "2") (pinfunction "2_2") (pintype "passive"))
    )
    (net (code "90") (name "Net-(OP4B-IN-)") (class "Default")
      (node (ref "OP4") (pin "6") (pinfunction "IN-_6") (pintype "input"))
      (node (ref "R102") (pin "2") (pinfunction "2_2") (pintype "passive"))
      (node (ref "R103") (pin "1") (pinfunction "1_1") (pintype "passive"))
    )
    (net (code "91") (name "Net-(OSC1-OUT)") (class "Default")
      (node (ref "OSC1") (pin "3") (pinfunction "OUT_3") (pintype "output"))
      (node (ref "U2") (pin "5") (pinfunction "PH0-OSC_IN_5") (pintype "bidirectional"))
    )
    (net (code "92") (name "Net-(R2COMP1-Pad2)") (class "Default")
      (node (ref "R2COMP1") (pin "2") (pinfunction "2_2") (pintype "passive"))
      (node (ref "R2COMP1_ADJ") (pin "2") (pinfunction "2_2") (pintype "passive"))
    )
    (net (code "93") (name "Net-(R2COMP1_ADJ1-Pad2)") (class "Default")
      (node (ref "R2COMP1_ADJ1") (pin "2") (pinfunction "2_2") (pintype "passive"))
      (node (ref "R2COMP3") (pin "2") (pinfunction "2_2") (pintype "passive"))
    )
    (net (code "94") (name "Net-(R2COMP2-Pad2)") (class "Default")
      (node (ref "R2COMP2") (pin "2") (pinfunction "2_2") (pintype "passive"))
      (node (ref "R2COMP2_ADJ") (pin "2") (pinfunction "2_2") (pintype "passive"))
    )
    (net (code "95") (name "Net-(R2COMP2_ADJ1-Pad2)") (class "Default")
      (node (ref "R2COMP2_ADJ1") (pin "2") (pinfunction "2_2") (pintype "passive"))
      (node (ref "R2COMP4") (pin "2") (pinfunction "2_2") (pintype "passive"))
    )
    (net (code "96") (name "Net-(R2V-Pad1)") (class "Default")
      (node (ref "R2V") (pin "1") (pinfunction "1_1") (pintype "passive"))
      (node (ref "R2V_ADJ") (pin "1") (pinfunction "1_1") (pintype "passive"))
    )
    (net (code "97") (name "Net-(R23-Pad1)") (class "Default")
      (node (ref "R23") (pin "1") (pinfunction "1_1") (pintype "passive"))
      (node (ref "R86") (pin "1") (pinfunction "1_1") (pintype "passive"))
    )
    (net (code "98") (name "Net-(R27-Pad2)") (class "Default")
      (node (ref "R27") (pin "2") (pinfunction "2_2") (pintype "passive"))
      (node (ref "RED17") (pin "C") (pinfunction "C_C") (pintype "passive"))
    )
    (net (code "99") (name "Net-(R29-Pad2)") (class "Default")
      (node (ref "R29") (pin "2") (pinfunction "2_2") (pintype "passive"))
      (node (ref "RED18") (pin "C") (pinfunction "C_C") (pintype "passive"))
    )
    (net (code "100") (name "Net-(U2-VCAP_1)") (class "Default")
      (node (ref "C29") (pin "1") (pinfunction "1_1") (pintype "passive"))
      (node (ref "U2") (pin "30") (pinfunction "VCAP_1_30") (pintype "power_in"))
    )
    (net (code "101") (name "Net-(USB1-D+)") (class "Default")
      (node (ref "IC1") (pin "3") (pinfunction "IO2_3") (pintype "bidirectional"))
      (node (ref "USB1") (pin "3") (pinfunction "D+_3") (pintype "passive"))
    )
    (net (code "102") (name "Net-(USB1-D-)") (class "Default")
      (node (ref "IC1") (pin "1") (pinfunction "IO1_1") (pintype "bidirectional"))
      (node (ref "USB1") (pin "2") (pinfunction "D-_2") (pintype "passive"))
    )
    (net (code "103") (name "Net-(USB1-P1)") (class "Default")
      (node (ref "R81") (pin "2") (pinfunction "2_2") (pintype "passive"))
      (node (ref "USB1") (pin "7") (pinfunction "P1_7") (pintype "passive"))
    )
    (net (code "104") (name "Net-(X1A-S)") (class "Default")
      (node (ref "JP3") (pin "2") (pinfunction "2_2") (pintype "passive"))
      (node (ref "X1") (pin "1") (pinfunction "S_1") (pintype "passive"))
      (node (ref "X1") (pin "2") (pinfunction "S_2") (pintype "passive"))
    )
    (net (code "105") (name "Net-(X1C-S)") (class "Default")
      (node (ref "JP4") (pin "2") (pinfunction "2_2") (pintype "passive"))
      (node (ref "X1") (pin "3") (pinfunction "S_3") (pintype "passive"))
      (node (ref "X1") (pin "4") (pinfunction "S_4") (pintype "passive"))
    )
    (net (code "106") (name "PPULSE_DETECT_I") (class "Default")
      (node (ref "COMP3") (pin "1") (pinfunction "OUT_1") (pintype "output"))
      (node (ref "RED17") (pin "A") (pinfunction "A_A") (pintype "passive"))
      (node (ref "U2") (pin "27") (pinfunction "PB1_27") (pintype "bidirectional"))
    )
    (net (code "107") (name "PPULSE_DETECT_V") (class "Default")
      (node (ref "COMP1") (pin "1") (pinfunction "OUT_1") (pintype "output"))
      (node (ref "RED18") (pin "A") (pinfunction "A_A") (pintype "passive"))
      (node (ref "U2") (pin "14") (pinfunction "PA0_14") (pintype "bidirectional"))
    )
    (net (code "108") (name "RESET") (class "Default")
      (node (ref "R39") (pin "1") (pinfunction "1_1") (pintype "passive"))
      (node (ref "U2") (pin "7") (pinfunction "NRST_7") (pintype "bidirectional"))
      (node (ref "X3") (pin "P5") (pinfunction "5_P5") (pintype "bidirectional"))
    )
    (net (code "109") (name "SC_N1") (class "Default")
      (node (ref "C21") (pin "1") (pinfunction "1_1") (pintype "passive"))
      (node (ref "OK21") (pin "4") (pinfunction "OUT_4") (pintype "output"))
      (node (ref "R47") (pin "2") (pinfunction "2_2") (pintype "passive"))
      (node (ref "U2") (pin "2") (pinfunction "PC13_2") (pintype "bidirectional"))
    )
    (net (code "110") (name "SC_N2") (class "Default")
      (node (ref "C22") (pin "1") (pinfunction "1_1") (pintype "passive"))
      (node (ref "OK22") (pin "4") (pinfunction "OUT_4") (pintype "output"))
      (node (ref "R50") (pin "2") (pinfunction "2_2") (pintype "passive"))
      (node (ref "U2") (pin "3") (pinfunction "PC14-OSC32_IN_3") (pintype "bidirectional"))
    )
    (net (code "111") (name "SC_N3") (class "Default")
      (node (ref "C23") (pin "1") (pinfunction "1_1") (pintype "passive"))
      (node (ref "OK23") (pin "4") (pinfunction "OUT_4") (pintype "output"))
      (node (ref "R52") (pin "2") (pinfunction "2_2") (pintype "passive"))
      (node (ref "U2") (pin "8") (pinfunction "PC0_8") (pintype "bidirectional"))
    )
    (net (code "112") (name "SC_N4") (class "Default")
      (node (ref "C24") (pin "1") (pinfunction "1_1") (pintype "passive"))
      (node (ref "OK24") (pin "4") (pinfunction "OUT_4") (pintype "output"))
      (node (ref "R54") (pin "2") (pinfunction "2_2") (pintype "passive"))
      (node (ref "U2") (pin "9") (pinfunction "PC1_9") (pintype "bidirectional"))
    )
    (net (code "113") (name "SC_P1") (class "Default")
      (node (ref "C9") (pin "1") (pinfunction "1_1") (pintype "passive"))
      (node (ref "OK9") (pin "4") (pinfunction "OUT_4") (pintype "output"))
      (node (ref "R26") (pin "2") (pinfunction "2_2") (pintype "passive"))
      (node (ref "U2") (pin "33") (pinfunction "PB12_33") (pintype "bidirectional"))
    )
    (net (code "114") (name "SC_P2") (class "Default")
      (node (ref "C4") (pin "1") (pinfunction "1_1") (pintype "passive"))
      (node (ref "OK4") (pin "4") (pinfunction "OUT_4") (pintype "output"))
      (node (ref "R12") (pin "2") (pinfunction "2_2") (pintype "passive"))
      (node (ref "U2") (pin "23") (pinfunction "PA7_23") (pintype "bidirectional"))
    )
    (net (code "115") (name "SC_P3") (class "Default")
      (node (ref "C6") (pin "1") (pinfunction "1_1") (pintype "passive"))
      (node (ref "OK6") (pin "4") (pinfunction "OUT_4") (pintype "output"))
      (node (ref "R16") (pin "2") (pinfunction "2_2") (pintype "passive"))
      (node (ref "U2") (pin "24") (pinfunction "PC4_24") (pintype "bidirectional"))
    )
    (net (code "116") (name "SC_P4") (class "Default")
      (node (ref "C7") (pin "1") (pinfunction "1_1") (pintype "passive"))
      (node (ref "OK7") (pin "4") (pinfunction "OUT_4") (pintype "output"))
      (node (ref "R18") (pin "2") (pinfunction "2_2") (pintype "passive"))
      (node (ref "U2") (pin "25") (pinfunction "PC5_25") (pintype "bidirectional"))
    )
    (net (code "117") (name "SPI1_MISO") (class "Default")
      (node (ref "SJ1") (pin "3") (pinfunction "3_3") (pintype "passive"))
      (node (ref "U2") (pin "22") (pinfunction "PA6_22") (pintype "bidirectional"))
    )
    (net (code "118") (name "SPI1_SCK") (class "Default")
      (node (ref "R28") (pin "1") (pinfunction "1_1") (pintype "passive"))
      (node (ref "U2") (pin "21") (pinfunction "PA5_21") (pintype "bidirectional"))
      (node (ref "U2") (pin "26") (pinfunction "PB0_26") (pintype "bidirectional"))
      (node (ref "U2") (pin "34") (pinfunction "PB13_34") (pintype "bidirectional"))
    )
    (net (code "119") (name "SPI4_MOSI") (class "Default")
      (node (ref "R24") (pin "1") (pinfunction "1_1") (pintype "passive"))
      (node (ref "U2") (pin "15") (pinfunction "PA1_15") (pintype "bidirectional"))
    )
    (net (code "120") (name "SPI5_MOSI") (class "Default")
      (node (ref "SJ1") (pin "1") (pinfunction "1_1") (pintype "passive"))
      (node (ref "U2") (pin "43") (pinfunction "PA10_43") (pintype "bidirectional"))
    )
    (net (code "121") (name "STIMN") (class "Default")
      (node (ref "G10") (pin "C") (pinfunction "C_C") (pintype "passive"))
      (node (ref "G11") (pin "C") (pinfunction "C_C") (pintype "passive"))
      (node (ref "G12") (pin "C") (pinfunction "C_C") (pintype "passive"))
      (node (ref "G13") (pin "C") (pinfunction "C_C") (pintype "passive"))
      (node (ref "G14") (pin "C") (pinfunction "C_C") (pintype "passive"))
      (node (ref "G15") (pin "C") (pinfunction "C_C") (pintype "passive"))
      (node (ref "G16") (pin "C") (pinfunction "C_C") (pintype "passive"))
      (node (ref "G9") (pin "C") (pinfunction "C_C") (pintype "passive"))
      (node (ref "J1") (pin "1") (pinfunction "S_1") (pintype "passive"))
      (node (ref "JP10") (pin "1") (pinfunction "1_1") (pintype "passive"))
      (node (ref "JP2") (pin "1") (pinfunction "1_1") (pintype "passive"))
      (node (ref "JP4") (pin "1") (pinfunction "1_1") (pintype "passive"))
      (node (ref "JP6") (pin "1") (pinfunction "1_1") (pintype "passive"))
      (node (ref "JP8") (pin "1") (pinfunction "1_1") (pintype "passive"))
      (node (ref "R1V") (pin "2") (pinfunction "2_2") (pintype "passive"))
      (node (ref "R46") (pin "2") (pinfunction "2_2") (pintype "passive"))
      (node (ref "R49") (pin "2") (pinfunction "2_2") (pintype "passive"))
      (node (ref "R51") (pin "2") (pinfunction "2_2") (pintype "passive"))
      (node (ref "R53") (pin "2") (pinfunction "2_2") (pintype "passive"))
      (node (ref "RED10") (pin "A") (pinfunction "A_A") (pintype "passive"))
      (node (ref "RED11") (pin "A") (pinfunction "A_A") (pintype "passive"))
      (node (ref "RED12") (pin "A") (pinfunction "A_A") (pintype "passive"))
      (node (ref "RED13") (pin "A") (pinfunction "A_A") (pintype "passive"))
      (node (ref "RED14") (pin "A") (pinfunction "A_A") (pintype "passive"))
      (node (ref "RED15") (pin "A") (pinfunction "A_A") (pintype "passive"))
      (node (ref "RED16") (pin "A") (pinfunction "A_A") (pintype "passive"))
      (node (ref "RED9") (pin "A") (pinfunction "A_A") (pintype "passive"))
    )
    (net (code "122") (name "STIMN_STIMULATOR1") (class "Default")
      (node (ref "G10") (pin "A") (pinfunction "A_A") (pintype "passive"))
      (node (ref "G9") (pin "A") (pinfunction "A_A") (pintype "passive"))
      (node (ref "OK21") (pin "2") (pinfunction "C_2") (pintype "passive"))
      (node (ref "RED10") (pin "C") (pinfunction "C_C") (pintype "passive"))
      (node (ref "RED9") (pin "C") (pinfunction "C_C") (pintype "passive"))
      (node (ref "XS5") (pin "1") (pinfunction "P_1") (pintype "passive"))
    )
    (net (code "123") (name "STIMN_STIMULATOR2") (class "Default")
      (node (ref "G11") (pin "A") (pinfunction "A_A") (pintype "passive"))
      (node (ref "G12") (pin "A") (pinfunction "A_A") (pintype "passive"))
      (node (ref "OK22") (pin "2") (pinfunction "C_2") (pintype "passive"))
      (node (ref "RED11") (pin "C") (pinfunction "C_C") (pintype "passive"))
      (node (ref "RED12") (pin "C") (pinfunction "C_C") (pintype "passive"))
      (node (ref "XS6") (pin "1") (pinfunction "P_1") (pintype "passive"))
    )
    (net (code "124") (name "STIMN_STIMULATOR3") (class "Default")
      (node (ref "G13") (pin "A") (pinfunction "A_A") (pintype "passive"))
      (node (ref "G14") (pin "A") (pinfunction "A_A") (pintype "passive"))
      (node (ref "OK23") (pin "2") (pinfunction "C_2") (pintype "passive"))
      (node (ref "RED13") (pin "C") (pinfunction "C_C") (pintype "passive"))
      (node (ref "RED14") (pin "C") (pinfunction "C_C") (pintype "passive"))
      (node (ref "XS7") (pin "1") (pinfunction "P_1") (pintype "passive"))
    )
    (net (code "125") (name "STIMN_STIMULATOR4") (class "Default")
      (node (ref "G15") (pin "A") (pinfunction "A_A") (pintype "passive"))
      (node (ref "G16") (pin "A") (pinfunction "A_A") (pintype "passive"))
      (node (ref "OK24") (pin "2") (pinfunction "C_2") (pintype "passive"))
      (node (ref "RED15") (pin "C") (pinfunction "C_C") (pintype "passive"))
      (node (ref "RED16") (pin "C") (pinfunction "C_C") (pintype "passive"))
      (node (ref "XS8") (pin "1") (pinfunction "P_1") (pintype "passive"))
    )
    (net (code "126") (name "STIMP") (class "Default")
      (node (ref "G1") (pin "A") (pinfunction "A_A") (pintype "passive"))
      (node (ref "G2") (pin "A") (pinfunction "A_A") (pintype "passive"))
      (node (ref "G3") (pin "A") (pinfunction "A_A") (pintype "passive"))
      (node (ref "G4") (pin "A") (pinfunction "A_A") (pintype "passive"))
      (node (ref "G5") (pin "A") (pinfunction "A_A") (pintype "passive"))
      (node (ref "G6") (pin "A") (pinfunction "A_A") (pintype "passive"))
      (node (ref "G7") (pin "A") (pinfunction "A_A") (pintype "passive"))
      (node (ref "G8") (pin "A") (pinfunction "A_A") (pintype "passive"))
      (node (ref "J3") (pin "3") (pinfunction "S_3") (pintype "passive"))
      (node (ref "OK4") (pin "2") (pinfunction "C_2") (pintype "passive"))
      (node (ref "OK6") (pin "2") (pinfunction "C_2") (pintype "passive"))
      (node (ref "OK7") (pin "2") (pinfunction "C_2") (pintype "passive"))
      (node (ref "OK9") (pin "2") (pinfunction "C_2") (pintype "passive"))
      (node (ref "R91") (pin "1") (pinfunction "1_1") (pintype "passive"))
      (node (ref "RED1") (pin "C") (pinfunction "C_C") (pintype "passive"))
      (node (ref "RED2") (pin "C") (pinfunction "C_C") (pintype "passive"))
      (node (ref "RED3") (pin "C") (pinfunction "C_C") (pintype "passive"))
      (node (ref "RED4") (pin "C") (pinfunction "C_C") (pintype "passive"))
      (node (ref "RED5") (pin "C") (pinfunction "C_C") (pintype "passive"))
      (node (ref "RED6") (pin "C") (pinfunction "C_C") (pintype "passive"))
      (node (ref "RED7") (pin "C") (pinfunction "C_C") (pintype "passive"))
      (node (ref "RED8") (pin "C") (pinfunction "C_C") (pintype "passive"))
      (node (ref "R_MESS") (pin "2") (pinfunction "2_2") (pintype "passive"))
      (node (ref "R_MESS_ADJ") (pin "1") (pinfunction "1_1") (pintype "passive"))
      (node (ref "SJ7") (pin "3") (pinfunction "3_3") (pintype "passive"))
    )
    (net (code "127") (name "STIMP_STIMULATOR1") (class "Default")
      (node (ref "G1") (pin "C") (pinfunction "C_C") (pintype "passive"))
      (node (ref "G2") (pin "C") (pinfunction "C_C") (pintype "passive"))
      (node (ref "R25") (pin "2") (pinfunction "2_2") (pintype "passive"))
      (node (ref "RED1") (pin "A") (pinfunction "A_A") (pintype "passive"))
      (node (ref "RED2") (pin "A") (pinfunction "A_A") (pintype "passive"))
      (node (ref "XS1") (pin "1") (pinfunction "P_1") (pintype "passive"))
    )
    (net (code "128") (name "STIMP_STIMULATOR2") (class "Default")
      (node (ref "G3") (pin "C") (pinfunction "C_C") (pintype "passive"))
      (node (ref "G4") (pin "C") (pinfunction "C_C") (pintype "passive"))
      (node (ref "R11") (pin "2") (pinfunction "2_2") (pintype "passive"))
      (node (ref "RED3") (pin "A") (pinfunction "A_A") (pintype "passive"))
      (node (ref "RED4") (pin "A") (pinfunction "A_A") (pintype "passive"))
      (node (ref "XS2") (pin "1") (pinfunction "P_1") (pintype "passive"))
    )
    (net (code "129") (name "STIMP_STIMULATOR3") (class "Default")
      (node (ref "G5") (pin "C") (pinfunction "C_C") (pintype "passive"))
      (node (ref "G6") (pin "C") (pinfunction "C_C") (pintype "passive"))
      (node (ref "R13") (pin "2") (pinfunction "2_2") (pintype "passive"))
      (node (ref "RED5") (pin "A") (pinfunction "A_A") (pintype "passive"))
      (node (ref "RED6") (pin "A") (pinfunction "A_A") (pintype "passive"))
      (node (ref "XS3") (pin "1") (pinfunction "P_1") (pintype "passive"))
    )
    (net (code "130") (name "STIMP_STIMULATOR4") (class "Default")
      (node (ref "G7") (pin "C") (pinfunction "C_C") (pintype "passive"))
      (node (ref "G8") (pin "C") (pinfunction "C_C") (pintype "passive"))
      (node (ref "R17") (pin "2") (pinfunction "2_2") (pintype "passive"))
      (node (ref "RED7") (pin "A") (pinfunction "A_A") (pintype "passive"))
      (node (ref "RED8") (pin "A") (pinfunction "A_A") (pintype "passive"))
      (node (ref "XS4") (pin "1") (pinfunction "P_1") (pintype "passive"))
    )
    (net (code "131") (name "SWDIO") (class "Default")
      (node (ref "U2") (pin "46") (pinfunction "PA13/SWDIO_46") (pintype "bidirectional"))
      (node (ref "X3") (pin "P4") (pinfunction "4_P4") (pintype "bidirectional"))
    )
    (net (code "132") (name "SWOUT") (class "Default")
      (node (ref "U2") (pin "55") (pinfunction "PB3_55") (pintype "bidirectional"))
      (node (ref "X3") (pin "P6") (pinfunction "6_P6") (pintype "bidirectional"))
    )
    (net (code "133") (name "SWSCK") (class "Default")
      (node (ref "U2") (pin "49") (pinfunction "PA14/SWSCK_49") (pintype "bidirectional"))
      (node (ref "X3") (pin "P2") (pinfunction "2_P2") (pintype "bidirectional"))
    )
    (net (code "134") (name "TIM3_CH3") (class "Default")
      (node (ref "SJ2") (pin "3") (pinfunction "3_3") (pintype "passive"))
      (node (ref "U2") (pin "39") (pinfunction "PC8_39") (pintype "bidirectional"))
    )
    (net (code "135") (name "USART3_RX") (class "Default")
      (node (ref "U2") (pin "52") (pinfunction "PC11_52") (pintype "bidirectional"))
      (node (ref "X2") (pin "P3") (pinfunction "3_P3") (pintype "bidirectional"))
    )
    (net (code "136") (name "USART3_TX") (class "Default")
      (node (ref "U2") (pin "51") (pinfunction "PC10_51") (pintype "bidirectional"))
      (node (ref "X2") (pin "P4") (pinfunction "4_P4") (pintype "bidirectional"))
    )
    (net (code "137") (name "USB_DM_MCU") (class "Default")
      (node (ref "ISO_1") (pin "11") (pinfunction "DD-_11") (pintype "bidirectional"))
      (node (ref "U2") (pin "44") (pinfunction "PA11_44") (pintype "bidirectional"))
    )
    (net (code "138") (name "USB_DP_MCU") (class "Default")
      (node (ref "ISO_1") (pin "10") (pinfunction "DD+_10") (pintype "bidirectional"))
      (node (ref "U2") (pin "45") (pinfunction "PA12_45") (pintype "bidirectional"))
    )
    (net (code "139") (name "VA_1") (class "Default")
      (node (ref "OP1") (pin "7") (pinfunction "OUT_7") (pintype "output"))
      (node (ref "OP2") (pin "3") (pinfunction "IN+_3") (pintype "input"))
      (node (ref "R5") (pin "2") (pinfunction "2_2") (pintype "passive"))
      (node (ref "R6") (pin "1") (pinfunction "1_1") (pintype "passive"))
      (node (ref "R7") (pin "1") (pinfunction "1_1") (pintype "passive"))
    )
    (net (code "140") (name "VA_2") (class "Default")
      (node (ref "COMP1") (pin "3") (pinfunction "+IN_3") (pintype "input"))
      (node (ref "COMP1") (pin "6") (pinfunction "-IN_6") (pintype "input"))
      (node (ref "OP3") (pin "7") (pinfunction "OUT_7") (pintype "output"))
      (node (ref "R103") (pin "2") (pinfunction "2_2") (pintype "passive"))
      (node (ref "R104") (pin "1") (pinfunction "1_1") (pintype "passive"))
      (node (ref "R105") (pin "1") (pinfunction "1_1") (pintype "passive"))
    )
    (net (code "141") (name "VB_1") (class "Default")
      (node (ref "OP2") (pin "7") (pinfunction "OUT_7") (pintype "output"))
      (node (ref "R3") (pin "2") (pinfunction "2_2") (pintype "passive"))
      (node (ref "R4") (pin "1") (pinfunction "1_1") (pintype "passive"))
    )
    (net (code "142") (name "VB_2") (class "Default")
      (node (ref "OP4") (pin "7") (pinfunction "OUT_7") (pintype "output"))
      (node (ref "R102") (pin "1") (pinfunction "1_1") (pintype "passive"))
      (node (ref "R85") (pin "2") (pinfunction "2_2") (pintype "passive"))
    )
    (net (code "143") (name "VREF") (class "Default")
      (node (ref "ADC1") (pin "14") (pinfunction "REFIN/OUT_14") (pintype "bidirectional"))
      (node (ref "C61") (pin "1") (pinfunction "1_1") (pintype "passive"))
      (node (ref "R84") (pin "1") (pinfunction "1_1") (pintype "passive"))
      (node (ref "U1") (pin "6") (pinfunction "VOUT_6") (pintype "output"))
    )
    (net (code "144") (name "VREF{slash}2") (class "Default")
      (node (ref "C60") (pin "1") (pinfunction "1_1") (pintype "passive"))
      (node (ref "OP2") (pin "5") (pinfunction "IN+_5") (pintype "input"))
      (node (ref "OP4") (pin "1") (pinfunction "OUT_1") (pintype "output"))
      (node (ref "OP4") (pin "2") (pinfunction "IN-_2") (pintype "input"))
      (node (ref "OP4") (pin "5") (pinfunction "IN+_5") (pintype "input"))
      (node (ref "R10") (pin "2") (pinfunction "2_2") (pintype "passive"))
      (node (ref "R108") (pin "2") (pinfunction "2_2") (pintype "passive"))
      (node (ref "TP14") (pin "TP") (pinfunction "TP_TP") (pintype "input"))
    )
    (net (code "145") (name "V_STIM") (class "Default")
      (node (ref "D2") (pin "3") (pinfunction "C1A2_3") (pintype "passive"))
      (node (ref "OP3") (pin "3") (pinfunction "IN+_3") (pintype "input"))
      (node (ref "R1V") (pin "1") (pinfunction "1_1") (pintype "passive"))
      (node (ref "R2V") (pin "2") (pinfunction "2_2") (pintype "passive"))
    )
    (net (code "146") (name "unconnected-(J1C-S-Pad2)") (class "Default")
      (node (ref "J1") (pin "2") (pinfunction "S_2") (pintype "passive"))
    )
    (net (code "147") (name "unconnected-(J3G-S-Pad4)") (class "Default")
      (node (ref "J3") (pin "4") (pinfunction "S_4") (pintype "passive"))
    )
    (net (code "148") (name "unconnected-(LDO1-FB-Pad4)") (class "Default")
      (node (ref "LDO1") (pin "4") (pinfunction "FB_4") (pintype "bidirectional"))
    )
    (net (code "149") (name "unconnected-(LDO2-FB-Pad4)") (class "Default")
      (node (ref "LDO2") (pin "4") (pinfunction "FB_4") (pintype "bidirectional"))
    )
    (net (code "150") (name "unconnected-(OSC1-TRI-Pad1)") (class "Default")
      (node (ref "OSC1") (pin "1") (pinfunction "TRI_1") (pintype "input"))
    )
    (net (code "151") (name "unconnected-(S1-Pad1)") (class "Default")
      (node (ref "S1") (pin "1") (pinfunction "1_1") (pintype "passive"))
    )
    (net (code "152") (name "unconnected-(S1-Pad3)") (class "Default")
      (node (ref "S1") (pin "3") (pinfunction "3_3") (pintype "passive"))
    )
    (net (code "153") (name "unconnected-(U1-DNC-Pad3)") (class "Default")
      (node (ref "U1") (pin "3") (pinfunction "DNC_3") (pintype "no_connect"))
    )
    (net (code "154") (name "unconnected-(U1-DNC_2-Pad5)") (class "Default")
      (node (ref "U1") (pin "5") (pinfunction "DNC_2_5") (pintype "no_connect"))
    )
    (net (code "155") (name "unconnected-(U2-PA9-Pad42)") (class "Default")
      (node (ref "U2") (pin "42") (pinfunction "PA9_42") (pintype "bidirectional"))
    )
    (net (code "156") (name "unconnected-(U2-PC15-OSC32_OUT-Pad4)") (class "Default")
      (node (ref "U2") (pin "4") (pinfunction "PC15-OSC32_OUT_4") (pintype "bidirectional"))
    )
    (net (code "157") (name "unconnected-(U2-PH1-OSC_OUT-Pad6)") (class "Default")
      (node (ref "U2") (pin "6") (pinfunction "PH1-OSC_OUT_6") (pintype "bidirectional"))
    )
    (net (code "158") (name "unconnected-(USB1-ID-Pad4)") (class "Default")
      (node (ref "USB1") (pin "4") (pinfunction "ID_4") (pintype "passive"))
    )
    (net (code "159") (name "unconnected-(USB1-P2-Pad8)") (class "Default")
      (node (ref "USB1") (pin "8") (pinfunction "P2_8") (pintype "passive"))
    )
    (net (code "160") (name "unconnected-(USB1-P3-Pad9)") (class "Default")
      (node (ref "USB1") (pin "9") (pinfunction "P3_9") (pintype "passive"))
    )
    (net (code "161") (name "unconnected-(USB1-P4-Pad10)") (class "Default")
      (node (ref "USB1") (pin "10") (pinfunction "P4_10") (pintype "passive"))
    )
  )
)
